# Sheet1.net
KiCad netlist of a schematic drawn in Altium Designer
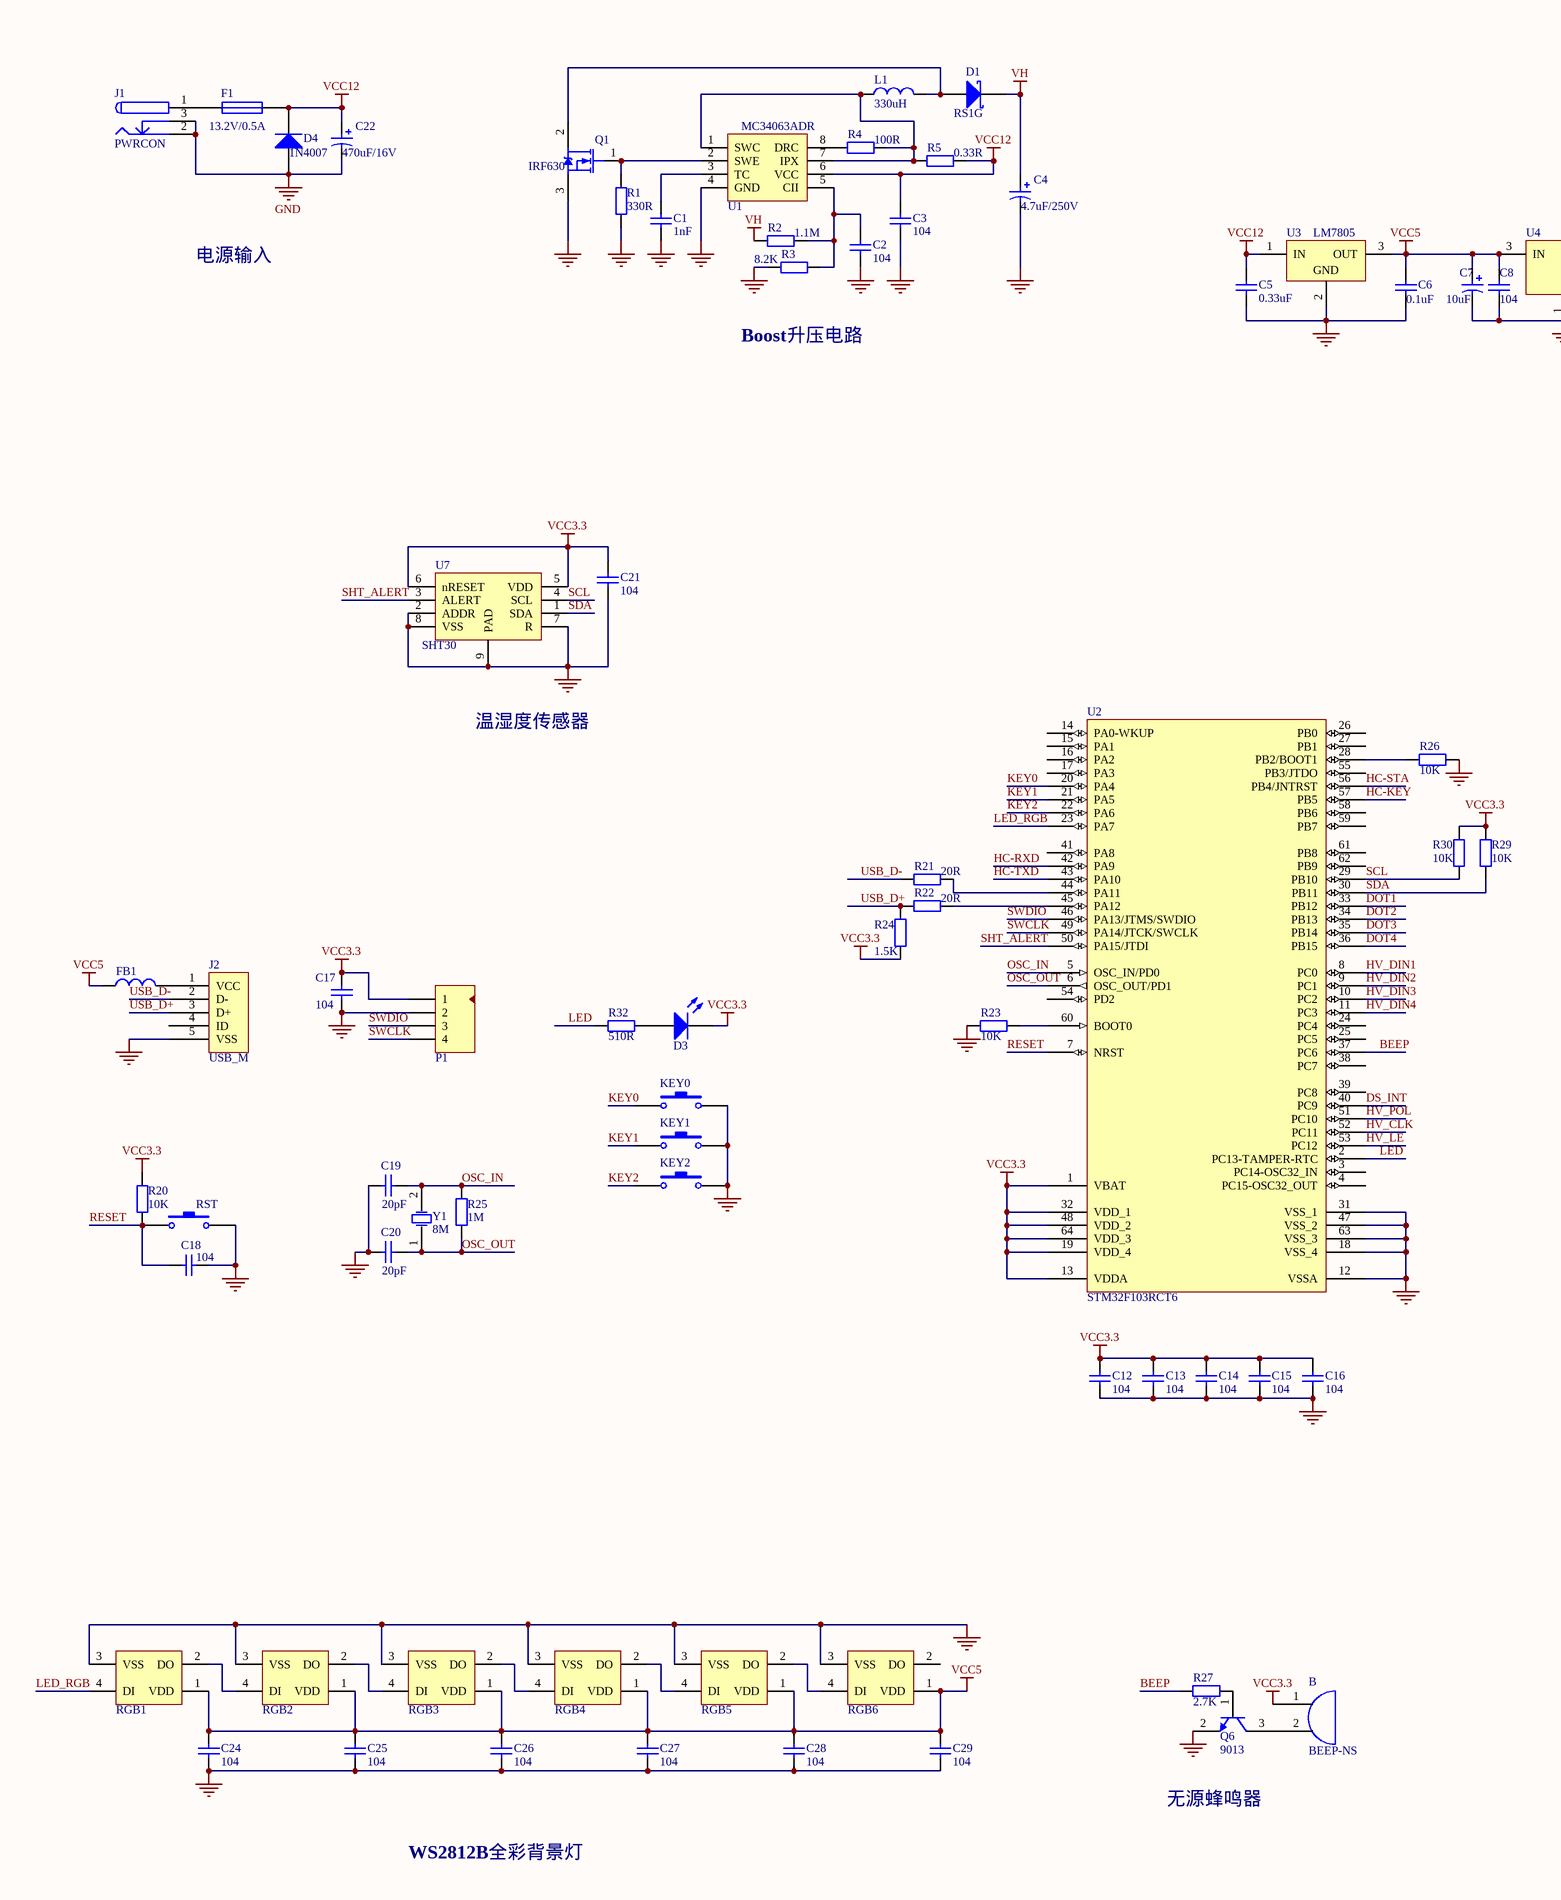
[diagram p0: Sheet1.SchDoc, left]
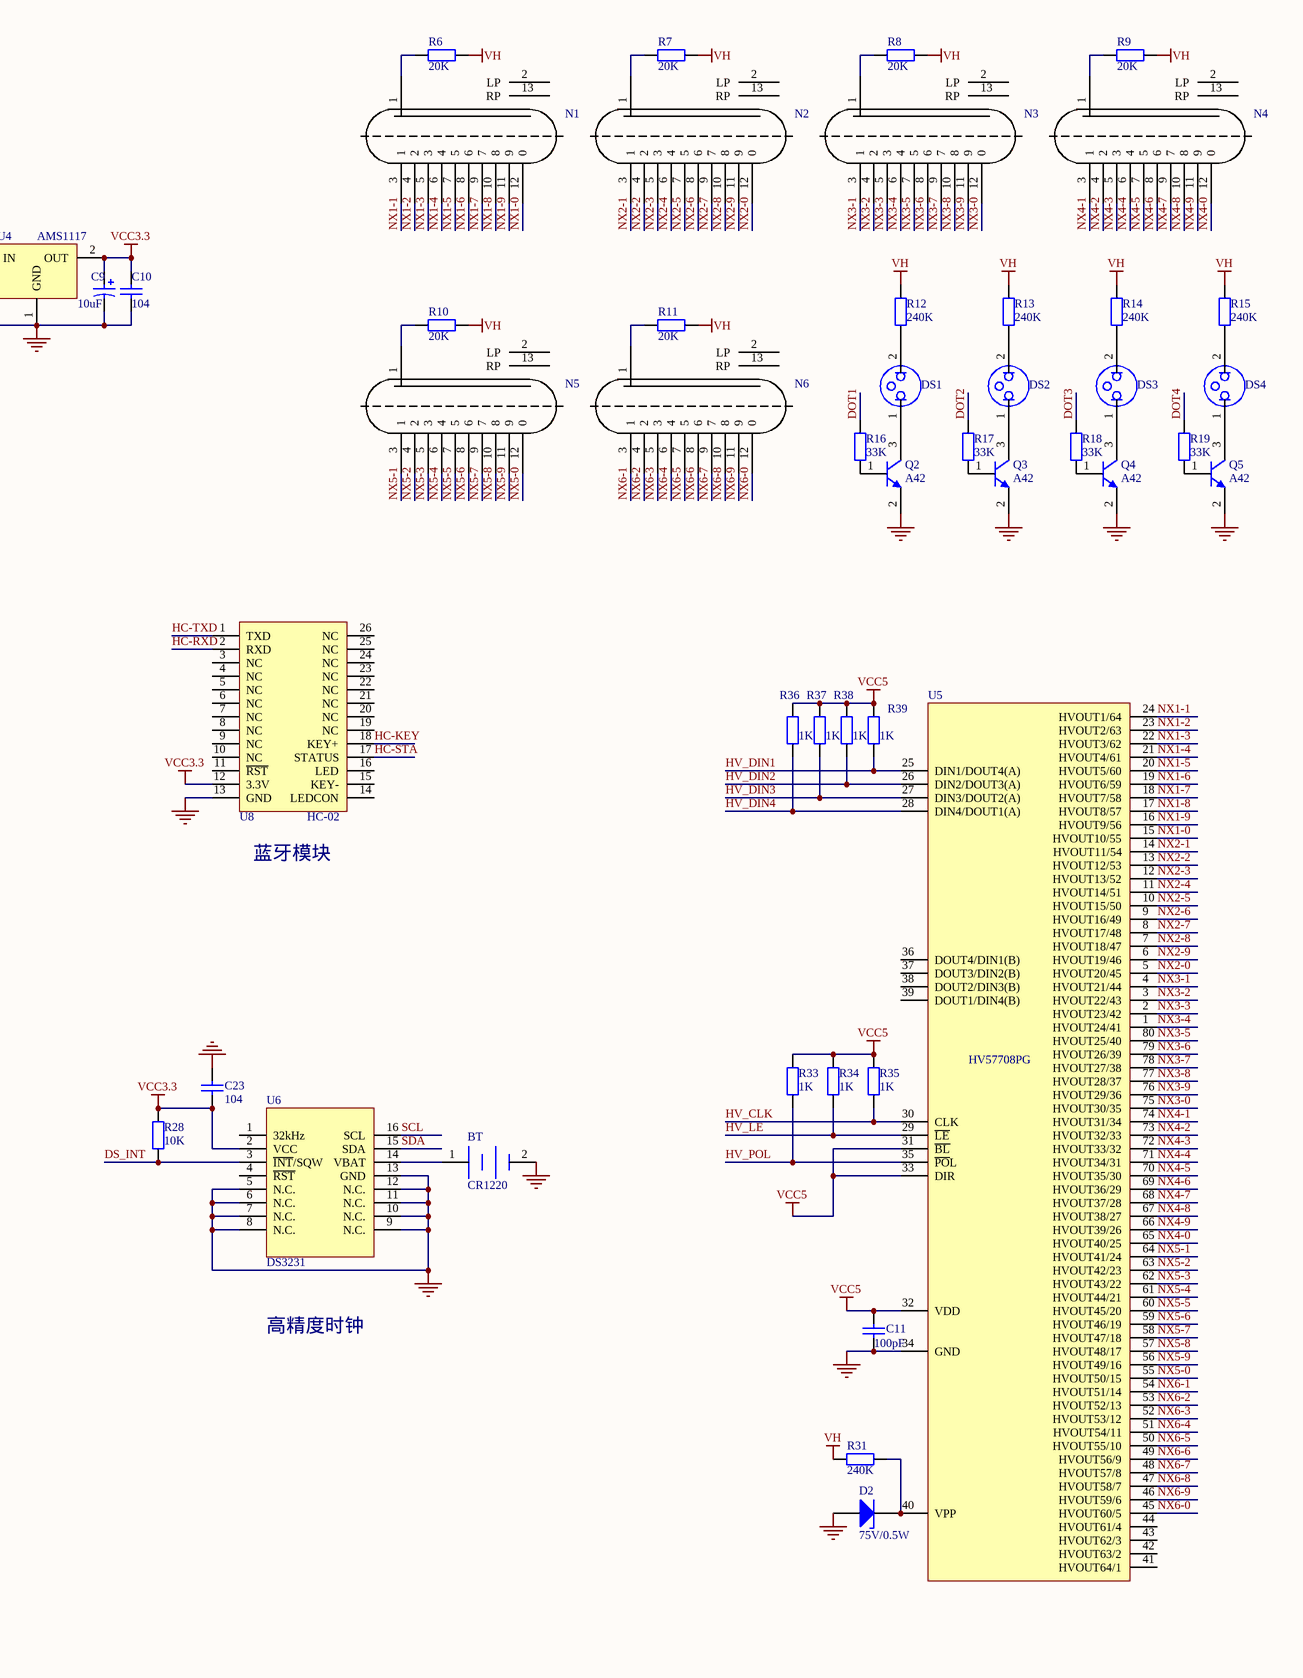
[diagram p1: Sheet1.SchDoc, right]

(export (version "E")
  (design (tool "Eeschema 10.0.6"))
  (components
    (comp (ref "B")
      (value "BEEP-NS")
      (footprint "BEEP-NS")
      (description "无源蜂鸣器")
      (libsource (lib "ChunLee") (part "BEEP-NS"))
    )
    (comp (ref "BT")
      (value "Battery")
      (footprint "CR1220")
      (fields (field (name "TYPE") "CR1220"))
      (libsource (lib "ChunLee") (part "Battery"))
    )
    (comp (ref "C1")
      (value "1nF")
      (footprint "C-0805")
      (description "贴片瓷片电容")
      (fields (field (name "Comment") "Cap-S") (field (name "PUBLISHER") "Altium Limited"))
      (libsource (lib "ChunLee") (part "Cap-S"))
    )
    (comp (ref "C2")
      (value "104")
      (footprint "C-0805")
      (description "贴片瓷片电容")
      (fields (field (name "Comment") "Cap-S") (field (name "PUBLISHER") "Altium Limited"))
      (libsource (lib "ChunLee") (part "Cap-S"))
    )
    (comp (ref "C3")
      (value "104")
      (footprint "C-0805")
      (description "贴片瓷片电容")
      (fields (field (name "Comment") "Cap-S") (field (name "PUBLISHER") "Altium Limited"))
      (libsource (lib "ChunLee") (part "Cap-S"))
    )
    (comp (ref "C4")
      (value "4.7uF/250V")
      (footprint "C-1812")
      (description "钽电容")
      (fields (field (name "Comment") "Cap-Pol") (field (name "PUBLISHER") "Altium Limited"))
      (libsource (lib "ChunLee") (part "Cap-Pol-A"))
    )
    (comp (ref "C5")
      (value "0.33uF")
      (footprint "C-1210")
      (description "贴片瓷片电容")
      (fields (field (name "Comment") "Cap-S") (field (name "PUBLISHER") "Altium Limited"))
      (libsource (lib "ChunLee") (part "Cap-S"))
    )
    (comp (ref "C6")
      (value "0.1uF")
      (footprint "C-1210")
      (description "贴片瓷片电容")
      (fields (field (name "Comment") "Cap-S") (field (name "PUBLISHER") "Altium Limited"))
      (libsource (lib "ChunLee") (part "Cap-S"))
    )
    (comp (ref "C7")
      (value "10uF")
      (footprint "C-1210")
      (description "钽电容")
      (fields (field (name "Comment") "Cap-Pol") (field (name "PUBLISHER") "Altium Limited"))
      (libsource (lib "ChunLee") (part "Cap-Pol-A"))
    )
    (comp (ref "C8")
      (value "104")
      (footprint "C-0805")
      (description "贴片瓷片电容")
      (fields (field (name "Comment") "Cap-S") (field (name "PUBLISHER") "Altium Limited"))
      (libsource (lib "ChunLee") (part "Cap-S"))
    )
    (comp (ref "C9")
      (value "10uF")
      (footprint "C-1210")
      (description "钽电容")
      (fields (field (name "Comment") "Cap-Pol") (field (name "PUBLISHER") "Altium Limited"))
      (libsource (lib "ChunLee") (part "Cap-Pol-A"))
    )
    (comp (ref "C10")
      (value "104")
      (footprint "C-0805")
      (description "贴片瓷片电容")
      (fields (field (name "Comment") "Cap-S") (field (name "PUBLISHER") "Altium Limited"))
      (libsource (lib "ChunLee") (part "Cap-S"))
    )
    (comp (ref "C11")
      (value "100pF")
      (footprint "C-0805")
      (description "贴片瓷片电容")
      (fields (field (name "Comment") "Cap-S") (field (name "PUBLISHER") "Altium Limited"))
      (libsource (lib "ChunLee") (part "Cap-S"))
    )
    (comp (ref "C12")
      (value "104")
      (footprint "C-0805")
      (description "贴片瓷片电容")
      (fields (field (name "Comment") "Cap-S") (field (name "PUBLISHER") "Altium Limited"))
      (libsource (lib "ChunLee") (part "Cap-S"))
    )
    (comp (ref "C13")
      (value "104")
      (footprint "C-0805")
      (description "贴片瓷片电容")
      (fields (field (name "Comment") "Cap-S") (field (name "PUBLISHER") "Altium Limited"))
      (libsource (lib "ChunLee") (part "Cap-S"))
    )
    (comp (ref "C14")
      (value "104")
      (footprint "C-0805")
      (description "贴片瓷片电容")
      (fields (field (name "Comment") "Cap-S") (field (name "PUBLISHER") "Altium Limited"))
      (libsource (lib "ChunLee") (part "Cap-S"))
    )
    (comp (ref "C15")
      (value "104")
      (footprint "C-0805")
      (description "贴片瓷片电容")
      (fields (field (name "Comment") "Cap-S") (field (name "PUBLISHER") "Altium Limited"))
      (libsource (lib "ChunLee") (part "Cap-S"))
    )
    (comp (ref "C16")
      (value "104")
      (footprint "C-0805")
      (description "贴片瓷片电容")
      (fields (field (name "Comment") "Cap-S") (field (name "PUBLISHER") "Altium Limited"))
      (libsource (lib "ChunLee") (part "Cap-S"))
    )
    (comp (ref "C17")
      (value "104")
      (footprint "C-0805")
      (description "贴片瓷片电容")
      (fields (field (name "Comment") "Cap-S") (field (name "PUBLISHER") "Altium Limited"))
      (libsource (lib "ChunLee") (part "Cap-S"))
    )
    (comp (ref "C18")
      (value "104")
      (footprint "C-0805")
      (description "贴片瓷片电容")
      (fields (field (name "Comment") "Cap-S") (field (name "PUBLISHER") "Altium Limited"))
      (libsource (lib "ChunLee") (part "Cap-S"))
    )
    (comp (ref "C19")
      (value "20pF")
      (footprint "C-0805")
      (description "贴片瓷片电容")
      (fields (field (name "Comment") "Cap-S") (field (name "PUBLISHER") "Altium Limited"))
      (libsource (lib "ChunLee") (part "Cap-S"))
    )
    (comp (ref "C20")
      (value "20pF")
      (footprint "C-0805")
      (description "贴片瓷片电容")
      (fields (field (name "Comment") "Cap-S") (field (name "PUBLISHER") "Altium Limited"))
      (libsource (lib "ChunLee") (part "Cap-S"))
    )
    (comp (ref "C21")
      (value "104")
      (footprint "C-0805")
      (description "贴片瓷片电容")
      (fields (field (name "Comment") "Cap-S") (field (name "PUBLISHER") "Altium Limited"))
      (libsource (lib "ChunLee") (part "Cap-S"))
    )
    (comp (ref "C22")
      (value "470uF/16V")
      (footprint "C-RB-SMD8x10.5")
      (description "贴片铝电解电容")
      (fields (field (name "Comment") "Cap-Pol-ES") (field (name "PUBLISHER") "Altium Limited"))
      (libsource (lib "ChunLee") (part "Cap-Pol-ES"))
    )
    (comp (ref "C23")
      (value "104")
      (footprint "C-0805")
      (description "贴片瓷片电容")
      (fields (field (name "Comment") "Cap-S") (field (name "PUBLISHER") "Altium Limited"))
      (libsource (lib "ChunLee") (part "Cap-S"))
    )
    (comp (ref "C24")
      (value "104")
      (footprint "C-0805")
      (description "贴片瓷片电容")
      (fields (field (name "Comment") "Cap-S") (field (name "PUBLISHER") "Altium Limited"))
      (libsource (lib "ChunLee") (part "Cap-S"))
    )
    (comp (ref "C25")
      (value "104")
      (footprint "C-0805")
      (description "贴片瓷片电容")
      (fields (field (name "Comment") "Cap-S") (field (name "PUBLISHER") "Altium Limited"))
      (libsource (lib "ChunLee") (part "Cap-S"))
    )
    (comp (ref "C26")
      (value "104")
      (footprint "C-0805")
      (description "贴片瓷片电容")
      (fields (field (name "Comment") "Cap-S") (field (name "PUBLISHER") "Altium Limited"))
      (libsource (lib "ChunLee") (part "Cap-S"))
    )
    (comp (ref "C27")
      (value "104")
      (footprint "C-0805")
      (description "贴片瓷片电容")
      (fields (field (name "Comment") "Cap-S") (field (name "PUBLISHER") "Altium Limited"))
      (libsource (lib "ChunLee") (part "Cap-S"))
    )
    (comp (ref "C28")
      (value "104")
      (footprint "C-0805")
      (description "贴片瓷片电容")
      (fields (field (name "Comment") "Cap-S") (field (name "PUBLISHER") "Altium Limited"))
      (libsource (lib "ChunLee") (part "Cap-S"))
    )
    (comp (ref "C29")
      (value "104")
      (footprint "C-0805")
      (description "贴片瓷片电容")
      (fields (field (name "Comment") "Cap-S") (field (name "PUBLISHER") "Altium Limited"))
      (libsource (lib "ChunLee") (part "Cap-S"))
    )
    (comp (ref "D1")
      (value "RS1G")
      (footprint "D-SMA")
      (description "快恢复二极管")
      (fields (field (name "PUBLISHER") "Altium Limited"))
      (libsource (lib "ChunLee") (part "Diode-Schottky"))
    )
    (comp (ref "D2")
      (value "75V/0.5W")
      (footprint "D-ll34")
      (description "稳压二极管")
      (fields (field (name "Comment") "ZMM75") (field (name "PUBLISHER") "Altium Limited"))
      (libsource (lib "ChunLee") (part "Diode-Z"))
    )
    (comp (ref "D3")
      (value "LED0")
      (footprint "LED-0805")
      (description "发光二极管")
      (fields (field (name "PUBLISHER") "Altium Limited"))
      (libsource (lib "ChunLee") (part "LED0"))
    )
    (comp (ref "D4")
      (value "1N4007")
      (footprint "D-SMA")
      (description "整流二极管")
      (fields (field (name "PUBLISHER") "Altium Limited"))
      (libsource (lib "ChunLee") (part "Diode"))
    )
    (comp (ref "DS1")
      (value "Neon")
      (footprint "PIN2")
      (description "氖泡")
      (libsource (lib "ChunLee") (part "Neon_Lamp"))
    )
    (comp (ref "DS2")
      (value "Neon")
      (footprint "PIN2")
      (description "氖泡")
      (libsource (lib "ChunLee") (part "Neon_Lamp"))
    )
    (comp (ref "DS3")
      (value "Neon")
      (footprint "PIN2")
      (description "氖泡")
      (libsource (lib "ChunLee") (part "Neon_Lamp"))
    )
    (comp (ref "DS4")
      (value "Neon")
      (footprint "PIN2")
      (description "氖泡")
      (libsource (lib "ChunLee") (part "Neon_Lamp"))
    )
    (comp (ref "F1")
      (value "13.2V/0.5A")
      (footprint "1206")
      (description "保险丝")
      (fields (field (name "Comment") "Fuse1"))
      (libsource (lib "ChunLee") (part "Fuse1"))
    )
    (comp (ref "FB1")
      (value "Inductor")
      (footprint "0805-1")
      (description "磁珠")
      (fields (field (name "PUBLISHER") "Altium Limited"))
      (libsource (lib "ChunLee") (part "Inductor"))
    )
    (comp (ref "J1")
      (value "PWRCON")
      (footprint "DC-005")
      (description "直流电源端子")
      (fields (field (name "PUBLISHER") "Altium Limited"))
      (libsource (lib "HDR_ChunLee") (part "PWRCON"))
    )
    (comp (ref "J2")
      (value "USB_M")
      (footprint "USB_MICRO")
      (description "Micro/Mini USB")
      (libsource (lib "HDR_ChunLee") (part "USB_M"))
    )
    (comp (ref "KEY0")
      (value "KEY")
      (footprint "SW_PB2_C1")
      (description "微动开关")
      (fields (field (name "PUBLISHER") "Altium Limited"))
      (libsource (lib "ChunLee") (part "SW-PB"))
    )
    (comp (ref "KEY1")
      (value "KEY")
      (footprint "SW_PB2_C1")
      (description "微动开关")
      (fields (field (name "PUBLISHER") "Altium Limited"))
      (libsource (lib "ChunLee") (part "SW-PB"))
    )
    (comp (ref "KEY2")
      (value "KEY")
      (footprint "SW_PB2_C1")
      (description "微动开关")
      (fields (field (name "PUBLISHER") "Altium Limited"))
      (libsource (lib "ChunLee") (part "SW-PB"))
    )
    (comp (ref "L1")
      (value "330uH")
      (footprint "L-SMD-12")
      (description "电感")
      (fields (field (name "Comment") "Inductor") (field (name "PUBLISHER") "Altium Limited"))
      (libsource (lib "ChunLee") (part "Inductor"))
    )
    (comp (ref "N1")
      (value "IN_14")
      (footprint "IN_14")
      (description "辉光管")
      (libsource (lib "ChunLee") (part "IN_14"))
    )
    (comp (ref "N2")
      (value "IN_14")
      (footprint "IN_14")
      (description "辉光管")
      (libsource (lib "ChunLee") (part "IN_14"))
    )
    (comp (ref "N3")
      (value "IN_14")
      (footprint "IN_14")
      (description "辉光管")
      (libsource (lib "ChunLee") (part "IN_14"))
    )
    (comp (ref "N4")
      (value "IN_14")
      (footprint "IN_14")
      (description "辉光管")
      (libsource (lib "ChunLee") (part "IN_14"))
    )
    (comp (ref "N5")
      (value "IN_14")
      (footprint "IN_14")
      (description "辉光管")
      (libsource (lib "ChunLee") (part "IN_14"))
    )
    (comp (ref "N6")
      (value "IN_14")
      (footprint "IN_14")
      (description "辉光管")
      (libsource (lib "ChunLee") (part "IN_14"))
    )
    (comp (ref "P1")
      (value "Header 4")
      (footprint "HDR4X1-2.54")
      (description "接插件")
      (fields (field (name "PUBLISHER") "Altium Limited"))
      (libsource (lib "HDR_ChunLee") (part "Header 4"))
    )
    (comp (ref "Q1")
      (value "IRF630")
      (footprint "TO263-2")
      (description "N-Channel MOSFET")
      (fields (field (name "PUBLISHER") "Altium Limited"))
      (libsource (lib "ChunLee") (part "MOSFET-N"))
    )
    (comp (ref "Q2")
      (value "A42")
      (footprint "SOT23-3")
      (description "贴片三极管")
      (fields (field (name "PUBLISHER") "Altium Limited"))
      (libsource (lib "ChunLee") (part "NPN1"))
    )
    (comp (ref "Q3")
      (value "A42")
      (footprint "SOT23-3")
      (description "贴片三极管")
      (fields (field (name "PUBLISHER") "Altium Limited"))
      (libsource (lib "ChunLee") (part "NPN1"))
    )
    (comp (ref "Q4")
      (value "A42")
      (footprint "SOT23-3")
      (description "贴片三极管")
      (fields (field (name "PUBLISHER") "Altium Limited"))
      (libsource (lib "ChunLee") (part "NPN1"))
    )
    (comp (ref "Q5")
      (value "A42")
      (footprint "SOT23-3")
      (description "贴片三极管")
      (fields (field (name "PUBLISHER") "Altium Limited"))
      (libsource (lib "ChunLee") (part "NPN1"))
    )
    (comp (ref "Q6")
      (value "9013")
      (footprint "SOT23-3")
      (description "贴片三极管")
      (fields (field (name "PUBLISHER") "Altium Limited"))
      (libsource (lib "ChunLee") (part "NPN1"))
    )
    (comp (ref "R1")
      (value "330R")
      (footprint "0805-1")
      (description "贴片电阻")
      (fields (field (name "Comment") "Res1") (field (name "PUBLISHER") "Altium Limited"))
      (libsource (lib "") (part "Res1_2"))
    )
    (comp (ref "R2")
      (value "1.1M")
      (footprint "0805-1")
      (description "贴片电阻")
      (fields (field (name "Comment") "Res1") (field (name "PUBLISHER") "Altium Limited"))
      (libsource (lib "") (part "Res1_1"))
    )
    (comp (ref "R3")
      (value "8.2K")
      (footprint "0805-1")
      (description "贴片电阻")
      (fields (field (name "Comment") "Res1") (field (name "PUBLISHER") "Altium Limited"))
      (libsource (lib "") (part "Res1_1"))
    )
    (comp (ref "R4")
      (value "100R")
      (footprint "0805-1")
      (description "贴片电阻")
      (fields (field (name "Comment") "Res1") (field (name "PUBLISHER") "Altium Limited"))
      (libsource (lib "") (part "Res1_1"))
    )
    (comp (ref "R5")
      (value "0.33R")
      (footprint "0805-1")
      (description "贴片电阻")
      (fields (field (name "Comment") "Res1") (field (name "PUBLISHER") "Altium Limited"))
      (libsource (lib "") (part "Res1_1"))
    )
    (comp (ref "R6")
      (value "20K")
      (footprint "0805-1")
      (description "贴片电阻")
      (fields (field (name "Comment") "Res1") (field (name "PUBLISHER") "Altium Limited"))
      (libsource (lib "") (part "Res1_1"))
    )
    (comp (ref "R7")
      (value "20K")
      (footprint "0805-1")
      (description "贴片电阻")
      (fields (field (name "Comment") "Res1") (field (name "PUBLISHER") "Altium Limited"))
      (libsource (lib "") (part "Res1_1"))
    )
    (comp (ref "R8")
      (value "20K")
      (footprint "0805-1")
      (description "贴片电阻")
      (fields (field (name "Comment") "Res1") (field (name "PUBLISHER") "Altium Limited"))
      (libsource (lib "") (part "Res1_1"))
    )
    (comp (ref "R9")
      (value "20K")
      (footprint "0805-1")
      (description "贴片电阻")
      (fields (field (name "Comment") "Res1") (field (name "PUBLISHER") "Altium Limited"))
      (libsource (lib "") (part "Res1_1"))
    )
    (comp (ref "R10")
      (value "20K")
      (footprint "0805-1")
      (description "贴片电阻")
      (fields (field (name "Comment") "Res1") (field (name "PUBLISHER") "Altium Limited"))
      (libsource (lib "") (part "Res1_1"))
    )
    (comp (ref "R11")
      (value "20K")
      (footprint "0805-1")
      (description "贴片电阻")
      (fields (field (name "Comment") "Res1") (field (name "PUBLISHER") "Altium Limited"))
      (libsource (lib "") (part "Res1_1"))
    )
    (comp (ref "R12")
      (value "240K")
      (footprint "0805-1")
      (description "贴片电阻")
      (fields (field (name "Comment") "Res1") (field (name "PUBLISHER") "Altium Limited"))
      (libsource (lib "ChunLee") (part "Res1"))
    )
    (comp (ref "R13")
      (value "240K")
      (footprint "0805-1")
      (description "贴片电阻")
      (fields (field (name "Comment") "Res1") (field (name "PUBLISHER") "Altium Limited"))
      (libsource (lib "ChunLee") (part "Res1"))
    )
    (comp (ref "R14")
      (value "240K")
      (footprint "0805-1")
      (description "贴片电阻")
      (fields (field (name "Comment") "Res1") (field (name "PUBLISHER") "Altium Limited"))
      (libsource (lib "") (part "Res1_2"))
    )
    (comp (ref "R15")
      (value "240K")
      (footprint "0805-1")
      (description "贴片电阻")
      (fields (field (name "Comment") "Res1") (field (name "PUBLISHER") "Altium Limited"))
      (libsource (lib "ChunLee") (part "Res1"))
    )
    (comp (ref "R16")
      (value "33K")
      (footprint "0805-1")
      (description "贴片电阻")
      (fields (field (name "Comment") "Res1") (field (name "PUBLISHER") "Altium Limited"))
      (libsource (lib "ChunLee") (part "Res1"))
    )
    (comp (ref "R17")
      (value "33K")
      (footprint "0805-1")
      (description "贴片电阻")
      (fields (field (name "Comment") "Res1") (field (name "PUBLISHER") "Altium Limited"))
      (libsource (lib "ChunLee") (part "Res1"))
    )
    (comp (ref "R18")
      (value "33K")
      (footprint "0805-1")
      (description "贴片电阻")
      (fields (field (name "Comment") "Res1") (field (name "PUBLISHER") "Altium Limited"))
      (libsource (lib "ChunLee") (part "Res1"))
    )
    (comp (ref "R19")
      (value "33K")
      (footprint "0805-1")
      (description "贴片电阻")
      (fields (field (name "Comment") "Res1") (field (name "PUBLISHER") "Altium Limited"))
      (libsource (lib "ChunLee") (part "Res1"))
    )
    (comp (ref "R20")
      (value "10K")
      (footprint "0805-1")
      (description "贴片电阻")
      (fields (field (name "Comment") "Res1") (field (name "PUBLISHER") "Altium Limited"))
      (libsource (lib "") (part "Res1_2"))
    )
    (comp (ref "R21")
      (value "20R")
      (footprint "0805-1")
      (description "贴片电阻")
      (fields (field (name "Comment") "Res1") (field (name "PUBLISHER") "Altium Limited"))
      (libsource (lib "") (part "Res1_1"))
    )
    (comp (ref "R22")
      (value "20R")
      (footprint "0805-1")
      (description "贴片电阻")
      (fields (field (name "Comment") "Res1") (field (name "PUBLISHER") "Altium Limited"))
      (libsource (lib "") (part "Res1_1"))
    )
    (comp (ref "R23")
      (value "10K")
      (footprint "0805-1")
      (description "贴片电阻")
      (fields (field (name "Comment") "Res1") (field (name "PUBLISHER") "Altium Limited"))
      (libsource (lib "") (part "Res1_1"))
    )
    (comp (ref "R24")
      (value "1.5K")
      (footprint "0805-1")
      (description "贴片电阻")
      (fields (field (name "Comment") "Res1") (field (name "PUBLISHER") "Altium Limited"))
      (libsource (lib "ChunLee") (part "Res1"))
    )
    (comp (ref "R25")
      (value "1M")
      (footprint "0805-1")
      (description "贴片电阻")
      (fields (field (name "Comment") "Res1") (field (name "PUBLISHER") "Altium Limited"))
      (libsource (lib "") (part "Res1_2"))
    )
    (comp (ref "R26")
      (value "10K")
      (footprint "0805-1")
      (description "贴片电阻")
      (fields (field (name "Comment") "Res1") (field (name "PUBLISHER") "Altium Limited"))
      (libsource (lib "") (part "Res1_1"))
    )
    (comp (ref "R27")
      (value "2.7K")
      (footprint "0805-1")
      (description "贴片电阻")
      (fields (field (name "Comment") "Res1") (field (name "PUBLISHER") "Altium Limited"))
      (libsource (lib "") (part "Res1_1"))
    )
    (comp (ref "R28")
      (value "10K")
      (footprint "0805-1")
      (description "贴片电阻")
      (fields (field (name "Comment") "Res1") (field (name "PUBLISHER") "Altium Limited"))
      (libsource (lib "") (part "Res1_2"))
    )
    (comp (ref "R29")
      (value "10K")
      (footprint "0805-1")
      (description "贴片电阻")
      (fields (field (name "Comment") "Res1") (field (name "PUBLISHER") "Altium Limited"))
      (libsource (lib "") (part "Res1_2"))
    )
    (comp (ref "R30")
      (value "10K")
      (footprint "0805-1")
      (description "贴片电阻")
      (fields (field (name "Comment") "Res1") (field (name "PUBLISHER") "Altium Limited"))
      (libsource (lib "") (part "Res1_2"))
    )
    (comp (ref "R31")
      (value "240K")
      (footprint "1206")
      (description "贴片电阻")
      (fields (field (name "Comment") "Res1") (field (name "PUBLISHER") "Altium Limited"))
      (libsource (lib "") (part "Res1_1"))
    )
    (comp (ref "R32")
      (value "510R")
      (footprint "0805-1")
      (description "贴片电阻")
      (fields (field (name "Comment") "Res1") (field (name "PUBLISHER") "Altium Limited"))
      (libsource (lib "") (part "Res1_1"))
    )
    (comp (ref "R33")
      (value "1K")
      (footprint "0805-1")
      (description "贴片电阻")
      (fields (field (name "Comment") "Res1") (field (name "PUBLISHER") "Altium Limited"))
      (libsource (lib "") (part "Res1_2"))
    )
    (comp (ref "R34")
      (value "1K")
      (footprint "0805-1")
      (description "贴片电阻")
      (fields (field (name "Comment") "Res1") (field (name "PUBLISHER") "Altium Limited"))
      (libsource (lib "") (part "Res1_2"))
    )
    (comp (ref "R35")
      (value "1K")
      (footprint "0805-1")
      (description "贴片电阻")
      (fields (field (name "Comment") "Res1") (field (name "PUBLISHER") "Altium Limited"))
      (libsource (lib "") (part "Res1_2"))
    )
    (comp (ref "R36")
      (value "1K")
      (footprint "0805-1")
      (description "贴片电阻")
      (fields (field (name "Comment") "Res1") (field (name "PUBLISHER") "Altium Limited"))
      (libsource (lib "") (part "Res1_2"))
    )
    (comp (ref "R37")
      (value "1K")
      (footprint "0805-1")
      (description "贴片电阻")
      (fields (field (name "Comment") "Res1") (field (name "PUBLISHER") "Altium Limited"))
      (libsource (lib "") (part "Res1_2"))
    )
    (comp (ref "R38")
      (value "1K")
      (footprint "0805-1")
      (description "贴片电阻")
      (fields (field (name "Comment") "Res1") (field (name "PUBLISHER") "Altium Limited"))
      (libsource (lib "") (part "Res1_2"))
    )
    (comp (ref "R39")
      (value "1K")
      (footprint "0805-1")
      (description "贴片电阻")
      (fields (field (name "Comment") "Res1") (field (name "PUBLISHER") "Altium Limited"))
      (libsource (lib "") (part "Res1_2"))
    )
    (comp (ref "RGB1")
      (value "WS2812B")
      (footprint "SMD-5050-4")
      (description "WS2812B 4脚RGB全彩LED")
      (libsource (lib "ChunLee") (part "WS2812B"))
    )
    (comp (ref "RGB2")
      (value "WS2812B")
      (footprint "SMD-5050-4")
      (description "WS2812B 4脚RGB全彩LED")
      (libsource (lib "ChunLee") (part "WS2812B"))
    )
    (comp (ref "RGB3")
      (value "WS2812B")
      (footprint "SMD-5050-4")
      (description "WS2812B 4脚RGB全彩LED")
      (libsource (lib "ChunLee") (part "WS2812B"))
    )
    (comp (ref "RGB4")
      (value "WS2812B")
      (footprint "SMD-5050-4")
      (description "WS2812B 4脚RGB全彩LED")
      (libsource (lib "ChunLee") (part "WS2812B"))
    )
    (comp (ref "RGB5")
      (value "WS2812B")
      (footprint "SMD-5050-4")
      (description "WS2812B 4脚RGB全彩LED")
      (libsource (lib "ChunLee") (part "WS2812B"))
    )
    (comp (ref "RGB6")
      (value "WS2812B")
      (footprint "SMD-5050-4")
      (description "WS2812B 4脚RGB全彩LED")
      (libsource (lib "ChunLee") (part "WS2812B"))
    )
    (comp (ref "RST")
      (value "SW-PB")
      (footprint "SW_PB2_A1")
      (description "微动开关")
      (fields (field (name "PUBLISHER") "Altium Limited"))
      (libsource (lib "ChunLee") (part "SW-PB"))
    )
    (comp (ref "U1")
      (value "MC34063ADR")
      (footprint "SOIC-8P")
      (description "开关变压器芯片")
      (libsource (lib "ChunLee") (part "MC34063ADR"))
    )
    (comp (ref "U2")
      (value "STM32F103RCT6")
      (footprint "LQFP-64")
      (description "STM32F103, 64引脚, 256Kb Flash, 48Kb SRAM")
      (fields (field (name "PUBLISHER") "Altium Limited"))
      (libsource (lib "ChunLee") (part "STM32F103RCT6"))
    )
    (comp (ref "U3")
      (value "LM7805")
      (footprint "DPAK")
      (description "Series 3-Terminal Positive Regulator")
      (libsource (lib "ChunLee") (part "LM7805CT"))
    )
    (comp (ref "U4")
      (value "AMS1117")
      (footprint "SOT223")
      (description "3.3V稳压芯片")
      (libsource (lib "ChunLee") (part "AMS1117"))
    )
    (comp (ref "U5")
      (value "HV57708PG")
      (footprint "PQFP-80")
      (description "32MHz, 64通道推挽输出串入并出芯片")
      (libsource (lib "ChunLee") (part "HV57708PG"))
    )
    (comp (ref "U6")
      (value "DS3231")
      (footprint "SOIC-16W")
      (description "高精度时钟芯片")
      (libsource (lib "ChunLee") (part "DS3231"))
    )
    (comp (ref "U7")
      (value "SHT30")
      (footprint "SHT3x-DIS")
      (description "温湿度传感器")
      (libsource (lib "ChunLee") (part "SHT3X"))
    )
    (comp (ref "U8")
      (value "HC-02")
      (footprint "HC-02")
      (description "串口蓝牙4.0, 10m")
      (libsource (lib "ChunLee") (part "HC-02"))
    )
    (comp (ref "Y1")
      (value "8M")
      (footprint "X-SM49")
      (description "晶振")
      (fields (field (name "Comment") "XTAL") (field (name "PUBLISHER") "Altium Limited"))
      (libsource (lib "ChunLee") (part "XTAL"))
    )
  )
  (nets
    (net (code "1") (name "/BEEP") (class "Default")
      (node (ref "R27") (pin "1") (pinfunction "1_1") (pintype "passive"))
      (node (ref "U2") (pin "37") (pinfunction "PC6_37") (pintype "bidirectional"))
    )
    (net (code "2") (name "/DOT1") (class "Default")
      (node (ref "R16") (pin "1") (pinfunction "1_1") (pintype "passive"))
      (node (ref "U2") (pin "33") (pinfunction "PB12_33") (pintype "bidirectional"))
    )
    (net (code "3") (name "/DOT2") (class "Default")
      (node (ref "R17") (pin "1") (pinfunction "1_1") (pintype "passive"))
      (node (ref "U2") (pin "34") (pinfunction "PB13_34") (pintype "bidirectional"))
    )
    (net (code "4") (name "/DOT3") (class "Default")
      (node (ref "R18") (pin "1") (pinfunction "1_1") (pintype "passive"))
      (node (ref "U2") (pin "35") (pinfunction "PB14_35") (pintype "bidirectional"))
    )
    (net (code "5") (name "/DOT4") (class "Default")
      (node (ref "R19") (pin "1") (pinfunction "1_1") (pintype "passive"))
      (node (ref "U2") (pin "36") (pinfunction "PB15_36") (pintype "bidirectional"))
    )
    (net (code "6") (name "/DS_INT") (class "Default")
      (node (ref "R28") (pin "1") (pinfunction "1_1") (pintype "passive"))
      (node (ref "U2") (pin "40") (pinfunction "PC9_40") (pintype "bidirectional"))
      (node (ref "U6") (pin "3") (pinfunction "~{INT}/SQW_3") (pintype "passive"))
    )
    (net (code "7") (name "/HC-KEY") (class "Default")
      (node (ref "U2") (pin "57") (pinfunction "PB5_57") (pintype "bidirectional"))
      (node (ref "U8") (pin "18") (pinfunction "KEY+_18") (pintype "passive"))
    )
    (net (code "8") (name "/HC-RXD") (class "Default")
      (node (ref "U2") (pin "42") (pinfunction "PA9_42") (pintype "bidirectional"))
      (node (ref "U8") (pin "2") (pinfunction "RXD_2") (pintype "passive"))
    )
    (net (code "9") (name "/HC-STA") (class "Default")
      (node (ref "U2") (pin "56") (pinfunction "PB4/JNTRST_56") (pintype "bidirectional"))
      (node (ref "U8") (pin "17") (pinfunction "STATUS_17") (pintype "passive"))
    )
    (net (code "10") (name "/HC-TXD") (class "Default")
      (node (ref "U2") (pin "43") (pinfunction "PA10_43") (pintype "bidirectional"))
      (node (ref "U8") (pin "1") (pinfunction "TXD_1") (pintype "passive"))
    )
    (net (code "11") (name "/HV_CLK") (class "Default")
      (node (ref "R35") (pin "1") (pinfunction "1_1") (pintype "passive"))
      (node (ref "U2") (pin "52") (pinfunction "PC11_52") (pintype "bidirectional"))
      (node (ref "U5") (pin "30") (pinfunction "CLK_30") (pintype "passive"))
    )
    (net (code "12") (name "/HV_DIN1") (class "Default")
      (node (ref "R39") (pin "1") (pinfunction "1_1") (pintype "passive"))
      (node (ref "U2") (pin "8") (pinfunction "PC0_8") (pintype "bidirectional"))
      (node (ref "U5") (pin "25") (pinfunction "DIN1/DOUT4(A)_25") (pintype "passive"))
    )
    (net (code "13") (name "/HV_DIN2") (class "Default")
      (node (ref "R38") (pin "1") (pinfunction "1_1") (pintype "passive"))
      (node (ref "U2") (pin "9") (pinfunction "PC1_9") (pintype "bidirectional"))
      (node (ref "U5") (pin "26") (pinfunction "DIN2/DOUT3(A)_26") (pintype "passive"))
    )
    (net (code "14") (name "/HV_DIN3") (class "Default")
      (node (ref "R37") (pin "1") (pinfunction "1_1") (pintype "passive"))
      (node (ref "U2") (pin "10") (pinfunction "PC2_10") (pintype "bidirectional"))
      (node (ref "U5") (pin "27") (pinfunction "DIN3/DOUT2(A)_27") (pintype "passive"))
    )
    (net (code "15") (name "/HV_DIN4") (class "Default")
      (node (ref "R36") (pin "1") (pinfunction "1_1") (pintype "passive"))
      (node (ref "U2") (pin "11") (pinfunction "PC3_11") (pintype "bidirectional"))
      (node (ref "U5") (pin "28") (pinfunction "DIN4/DOUT1(A)_28") (pintype "passive"))
    )
    (net (code "16") (name "/HV_LE") (class "Default")
      (node (ref "R34") (pin "1") (pinfunction "1_1") (pintype "passive"))
      (node (ref "U2") (pin "53") (pinfunction "PC12_53") (pintype "bidirectional"))
      (node (ref "U5") (pin "29") (pinfunction "~{LE}_29") (pintype "passive"))
    )
    (net (code "17") (name "/HV_POL") (class "Default")
      (node (ref "R33") (pin "1") (pinfunction "1_1") (pintype "passive"))
      (node (ref "U2") (pin "51") (pinfunction "PC10_51") (pintype "bidirectional"))
      (node (ref "U5") (pin "35") (pinfunction "~{PO}L_35") (pintype "passive"))
    )
    (net (code "18") (name "/KEY0") (class "Default")
      (node (ref "KEY0") (pin "1") (pinfunction "1_1") (pintype "passive"))
      (node (ref "U2") (pin "20") (pinfunction "PA4_20") (pintype "bidirectional"))
    )
    (net (code "19") (name "/KEY1") (class "Default")
      (node (ref "KEY1") (pin "1") (pinfunction "1_1") (pintype "passive"))
      (node (ref "U2") (pin "21") (pinfunction "PA5_21") (pintype "bidirectional"))
    )
    (net (code "20") (name "/KEY2") (class "Default")
      (node (ref "KEY2") (pin "1") (pinfunction "1_1") (pintype "passive"))
      (node (ref "U2") (pin "22") (pinfunction "PA6_22") (pintype "bidirectional"))
    )
    (net (code "21") (name "/LED") (class "Default")
      (node (ref "R32") (pin "1") (pinfunction "1_1") (pintype "passive"))
      (node (ref "U2") (pin "2") (pinfunction "PC13-TAMPER-RTC_2") (pintype "bidirectional"))
    )
    (net (code "22") (name "/LED_RGB") (class "Default")
      (node (ref "RGB1") (pin "4") (pinfunction "DI_4") (pintype "passive"))
      (node (ref "U2") (pin "23") (pinfunction "PA7_23") (pintype "bidirectional"))
    )
    (net (code "23") (name "/NX1-0") (class "Default")
      (node (ref "N1") (pin "12") (pinfunction "0_12") (pintype "passive"))
      (node (ref "U5") (pin "15") (pinfunction "HVOUT10/55_15") (pintype "passive"))
    )
    (net (code "24") (name "/NX1-1") (class "Default")
      (node (ref "N1") (pin "3") (pinfunction "1_3") (pintype "passive"))
      (node (ref "U5") (pin "24") (pinfunction "HVOUT1/64_24") (pintype "passive"))
    )
    (net (code "25") (name "/NX1-2") (class "Default")
      (node (ref "N1") (pin "4") (pinfunction "2_4") (pintype "passive"))
      (node (ref "U5") (pin "23") (pinfunction "HVOUT2/63_23") (pintype "passive"))
    )
    (net (code "26") (name "/NX1-3") (class "Default")
      (node (ref "N1") (pin "5") (pinfunction "3_5") (pintype "passive"))
      (node (ref "U5") (pin "22") (pinfunction "HVOUT3/62_22") (pintype "passive"))
    )
    (net (code "27") (name "/NX1-4") (class "Default")
      (node (ref "N1") (pin "6") (pinfunction "4_6") (pintype "passive"))
      (node (ref "U5") (pin "21") (pinfunction "HVOUT4/61_21") (pintype "passive"))
    )
    (net (code "28") (name "/NX1-5") (class "Default")
      (node (ref "N1") (pin "7") (pinfunction "5_7") (pintype "passive"))
      (node (ref "U5") (pin "20") (pinfunction "HVOUT5/60_20") (pintype "passive"))
    )
    (net (code "29") (name "/NX1-6") (class "Default")
      (node (ref "N1") (pin "8") (pinfunction "6_8") (pintype "passive"))
      (node (ref "U5") (pin "19") (pinfunction "HVOUT6/59_19") (pintype "passive"))
    )
    (net (code "30") (name "/NX1-7") (class "Default")
      (node (ref "N1") (pin "9") (pinfunction "7_9") (pintype "passive"))
      (node (ref "U5") (pin "18") (pinfunction "HVOUT7/58_18") (pintype "passive"))
    )
    (net (code "31") (name "/NX1-8") (class "Default")
      (node (ref "N1") (pin "10") (pinfunction "8_10") (pintype "passive"))
      (node (ref "U5") (pin "17") (pinfunction "HVOUT8/57_17") (pintype "passive"))
    )
    (net (code "32") (name "/NX1-9") (class "Default")
      (node (ref "N1") (pin "11") (pinfunction "9_11") (pintype "passive"))
      (node (ref "U5") (pin "16") (pinfunction "HVOUT9/56_16") (pintype "passive"))
    )
    (net (code "33") (name "/NX2-0") (class "Default")
      (node (ref "N2") (pin "12") (pinfunction "0_12") (pintype "passive"))
      (node (ref "U5") (pin "5") (pinfunction "HVOUT20/45_5") (pintype "passive"))
    )
    (net (code "34") (name "/NX2-1") (class "Default")
      (node (ref "N2") (pin "3") (pinfunction "1_3") (pintype "passive"))
      (node (ref "U5") (pin "14") (pinfunction "HVOUT11/54_14") (pintype "passive"))
    )
    (net (code "35") (name "/NX2-2") (class "Default")
      (node (ref "N2") (pin "4") (pinfunction "2_4") (pintype "passive"))
      (node (ref "U5") (pin "13") (pinfunction "HVOUT12/53_13") (pintype "passive"))
    )
    (net (code "36") (name "/NX2-3") (class "Default")
      (node (ref "N2") (pin "5") (pinfunction "3_5") (pintype "passive"))
      (node (ref "U5") (pin "12") (pinfunction "HVOUT13/52_12") (pintype "passive"))
    )
    (net (code "37") (name "/NX2-4") (class "Default")
      (node (ref "N2") (pin "6") (pinfunction "4_6") (pintype "passive"))
      (node (ref "U5") (pin "11") (pinfunction "HVOUT14/51_11") (pintype "passive"))
    )
    (net (code "38") (name "/NX2-5") (class "Default")
      (node (ref "N2") (pin "7") (pinfunction "5_7") (pintype "passive"))
      (node (ref "U5") (pin "10") (pinfunction "HVOUT15/50_10") (pintype "passive"))
    )
    (net (code "39") (name "/NX2-6") (class "Default")
      (node (ref "N2") (pin "8") (pinfunction "6_8") (pintype "passive"))
      (node (ref "U5") (pin "9") (pinfunction "HVOUT16/49_9") (pintype "passive"))
    )
    (net (code "40") (name "/NX2-7") (class "Default")
      (node (ref "N2") (pin "9") (pinfunction "7_9") (pintype "passive"))
      (node (ref "U5") (pin "8") (pinfunction "HVOUT17/48_8") (pintype "passive"))
    )
    (net (code "41") (name "/NX2-8") (class "Default")
      (node (ref "N2") (pin "10") (pinfunction "8_10") (pintype "passive"))
      (node (ref "U5") (pin "7") (pinfunction "HVOUT18/47_7") (pintype "passive"))
    )
    (net (code "42") (name "/NX2-9") (class "Default")
      (node (ref "N2") (pin "11") (pinfunction "9_11") (pintype "passive"))
      (node (ref "U5") (pin "6") (pinfunction "HVOUT19/46_6") (pintype "passive"))
    )
    (net (code "43") (name "/NX3-0") (class "Default")
      (node (ref "N3") (pin "12") (pinfunction "0_12") (pintype "passive"))
      (node (ref "U5") (pin "75") (pinfunction "HVOUT30/35_75") (pintype "passive"))
    )
    (net (code "44") (name "/NX3-1") (class "Default")
      (node (ref "N3") (pin "3") (pinfunction "1_3") (pintype "passive"))
      (node (ref "U5") (pin "4") (pinfunction "HVOUT21/44_4") (pintype "passive"))
    )
    (net (code "45") (name "/NX3-2") (class "Default")
      (node (ref "N3") (pin "4") (pinfunction "2_4") (pintype "passive"))
      (node (ref "U5") (pin "3") (pinfunction "HVOUT22/43_3") (pintype "passive"))
    )
    (net (code "46") (name "/NX3-3") (class "Default")
      (node (ref "N3") (pin "5") (pinfunction "3_5") (pintype "passive"))
      (node (ref "U5") (pin "2") (pinfunction "HVOUT23/42_2") (pintype "passive"))
    )
    (net (code "47") (name "/NX3-4") (class "Default")
      (node (ref "N3") (pin "6") (pinfunction "4_6") (pintype "passive"))
      (node (ref "U5") (pin "1") (pinfunction "HVOUT24/41_1") (pintype "passive"))
    )
    (net (code "48") (name "/NX3-5") (class "Default")
      (node (ref "N3") (pin "7") (pinfunction "5_7") (pintype "passive"))
      (node (ref "U5") (pin "80") (pinfunction "HVOUT25/40_80") (pintype "passive"))
    )
    (net (code "49") (name "/NX3-6") (class "Default")
      (node (ref "N3") (pin "8") (pinfunction "6_8") (pintype "passive"))
      (node (ref "U5") (pin "79") (pinfunction "HVOUT26/39_79") (pintype "passive"))
    )
    (net (code "50") (name "/NX3-7") (class "Default")
      (node (ref "N3") (pin "9") (pinfunction "7_9") (pintype "passive"))
      (node (ref "U5") (pin "78") (pinfunction "HVOUT27/38_78") (pintype "passive"))
    )
    (net (code "51") (name "/NX3-8") (class "Default")
      (node (ref "N3") (pin "10") (pinfunction "8_10") (pintype "passive"))
      (node (ref "U5") (pin "77") (pinfunction "HVOUT28/37_77") (pintype "passive"))
    )
    (net (code "52") (name "/NX3-9") (class "Default")
      (node (ref "N3") (pin "11") (pinfunction "9_11") (pintype "passive"))
      (node (ref "U5") (pin "76") (pinfunction "HVOUT29/36_76") (pintype "passive"))
    )
    (net (code "53") (name "/NX4-0") (class "Default")
      (node (ref "N4") (pin "12") (pinfunction "0_12") (pintype "passive"))
      (node (ref "U5") (pin "65") (pinfunction "HVOUT40/25_65") (pintype "passive"))
    )
    (net (code "54") (name "/NX4-1") (class "Default")
      (node (ref "N4") (pin "3") (pinfunction "1_3") (pintype "passive"))
      (node (ref "U5") (pin "74") (pinfunction "HVOUT31/34_74") (pintype "passive"))
    )
    (net (code "55") (name "/NX4-2") (class "Default")
      (node (ref "N4") (pin "4") (pinfunction "2_4") (pintype "passive"))
      (node (ref "U5") (pin "73") (pinfunction "HVOUT32/33_73") (pintype "passive"))
    )
    (net (code "56") (name "/NX4-3") (class "Default")
      (node (ref "N4") (pin "5") (pinfunction "3_5") (pintype "passive"))
      (node (ref "U5") (pin "72") (pinfunction "HVOUT33/32_72") (pintype "passive"))
    )
    (net (code "57") (name "/NX4-4") (class "Default")
      (node (ref "N4") (pin "6") (pinfunction "4_6") (pintype "passive"))
      (node (ref "U5") (pin "71") (pinfunction "HVOUT34/31_71") (pintype "passive"))
    )
    (net (code "58") (name "/NX4-5") (class "Default")
      (node (ref "N4") (pin "7") (pinfunction "5_7") (pintype "passive"))
      (node (ref "U5") (pin "70") (pinfunction "HVOUT35/30_70") (pintype "passive"))
    )
    (net (code "59") (name "/NX4-6") (class "Default")
      (node (ref "N4") (pin "8") (pinfunction "6_8") (pintype "passive"))
      (node (ref "U5") (pin "69") (pinfunction "HVOUT36/29_69") (pintype "passive"))
    )
    (net (code "60") (name "/NX4-7") (class "Default")
      (node (ref "N4") (pin "9") (pinfunction "7_9") (pintype "passive"))
      (node (ref "U5") (pin "68") (pinfunction "HVOUT37/28_68") (pintype "passive"))
    )
    (net (code "61") (name "/NX4-8") (class "Default")
      (node (ref "N4") (pin "10") (pinfunction "8_10") (pintype "passive"))
      (node (ref "U5") (pin "67") (pinfunction "HVOUT38/27_67") (pintype "passive"))
    )
    (net (code "62") (name "/NX4-9") (class "Default")
      (node (ref "N4") (pin "11") (pinfunction "9_11") (pintype "passive"))
      (node (ref "U5") (pin "66") (pinfunction "HVOUT39/26_66") (pintype "passive"))
    )
    (net (code "63") (name "/NX5-0") (class "Default")
      (node (ref "N5") (pin "12") (pinfunction "0_12") (pintype "passive"))
      (node (ref "U5") (pin "55") (pinfunction "HVOUT50/15_55") (pintype "passive"))
    )
    (net (code "64") (name "/NX5-1") (class "Default")
      (node (ref "N5") (pin "3") (pinfunction "1_3") (pintype "passive"))
      (node (ref "U5") (pin "64") (pinfunction "HVOUT41/24_64") (pintype "passive"))
    )
    (net (code "65") (name "/NX5-2") (class "Default")
      (node (ref "N5") (pin "4") (pinfunction "2_4") (pintype "passive"))
      (node (ref "U5") (pin "63") (pinfunction "HVOUT42/23_63") (pintype "passive"))
    )
    (net (code "66") (name "/NX5-3") (class "Default")
      (node (ref "N5") (pin "5") (pinfunction "3_5") (pintype "passive"))
      (node (ref "U5") (pin "62") (pinfunction "HVOUT43/22_62") (pintype "passive"))
    )
    (net (code "67") (name "/NX5-4") (class "Default")
      (node (ref "N5") (pin "6") (pinfunction "4_6") (pintype "passive"))
      (node (ref "U5") (pin "61") (pinfunction "HVOUT44/21_61") (pintype "passive"))
    )
    (net (code "68") (name "/NX5-5") (class "Default")
      (node (ref "N5") (pin "7") (pinfunction "5_7") (pintype "passive"))
      (node (ref "U5") (pin "60") (pinfunction "HVOUT45/20_60") (pintype "passive"))
    )
    (net (code "69") (name "/NX5-6") (class "Default")
      (node (ref "N5") (pin "8") (pinfunction "6_8") (pintype "passive"))
      (node (ref "U5") (pin "59") (pinfunction "HVOUT46/19_59") (pintype "passive"))
    )
    (net (code "70") (name "/NX5-7") (class "Default")
      (node (ref "N5") (pin "9") (pinfunction "7_9") (pintype "passive"))
      (node (ref "U5") (pin "58") (pinfunction "HVOUT47/18_58") (pintype "passive"))
    )
    (net (code "71") (name "/NX5-8") (class "Default")
      (node (ref "N5") (pin "10") (pinfunction "8_10") (pintype "passive"))
      (node (ref "U5") (pin "57") (pinfunction "HVOUT48/17_57") (pintype "passive"))
    )
    (net (code "72") (name "/NX5-9") (class "Default")
      (node (ref "N5") (pin "11") (pinfunction "9_11") (pintype "passive"))
      (node (ref "U5") (pin "56") (pinfunction "HVOUT49/16_56") (pintype "passive"))
    )
    (net (code "73") (name "/NX6-0") (class "Default")
      (node (ref "N6") (pin "12") (pinfunction "0_12") (pintype "passive"))
      (node (ref "U5") (pin "45") (pinfunction "HVOUT60/5_45") (pintype "passive"))
    )
    (net (code "74") (name "/NX6-1") (class "Default")
      (node (ref "N6") (pin "3") (pinfunction "1_3") (pintype "passive"))
      (node (ref "U5") (pin "54") (pinfunction "HVOUT51/14_54") (pintype "passive"))
    )
    (net (code "75") (name "/NX6-2") (class "Default")
      (node (ref "N6") (pin "4") (pinfunction "2_4") (pintype "passive"))
      (node (ref "U5") (pin "53") (pinfunction "HVOUT52/13_53") (pintype "passive"))
    )
    (net (code "76") (name "/NX6-3") (class "Default")
      (node (ref "N6") (pin "5") (pinfunction "3_5") (pintype "passive"))
      (node (ref "U5") (pin "52") (pinfunction "HVOUT53/12_52") (pintype "passive"))
    )
    (net (code "77") (name "/NX6-4") (class "Default")
      (node (ref "N6") (pin "6") (pinfunction "4_6") (pintype "passive"))
      (node (ref "U5") (pin "51") (pinfunction "HVOUT54/11_51") (pintype "passive"))
    )
    (net (code "78") (name "/NX6-5") (class "Default")
      (node (ref "N6") (pin "7") (pinfunction "5_7") (pintype "passive"))
      (node (ref "U5") (pin "50") (pinfunction "HVOUT55/10_50") (pintype "passive"))
    )
    (net (code "79") (name "/NX6-6") (class "Default")
      (node (ref "N6") (pin "8") (pinfunction "6_8") (pintype "passive"))
      (node (ref "U5") (pin "49") (pinfunction "HVOUT56/9_49") (pintype "passive"))
    )
    (net (code "80") (name "/NX6-7") (class "Default")
      (node (ref "N6") (pin "9") (pinfunction "7_9") (pintype "passive"))
      (node (ref "U5") (pin "48") (pinfunction "HVOUT57/8_48") (pintype "passive"))
    )
    (net (code "81") (name "/NX6-8") (class "Default")
      (node (ref "N6") (pin "10") (pinfunction "8_10") (pintype "passive"))
      (node (ref "U5") (pin "47") (pinfunction "HVOUT58/7_47") (pintype "passive"))
    )
    (net (code "82") (name "/NX6-9") (class "Default")
      (node (ref "N6") (pin "11") (pinfunction "9_11") (pintype "passive"))
      (node (ref "U5") (pin "46") (pinfunction "HVOUT59/6_46") (pintype "passive"))
    )
    (net (code "83") (name "/OSC_IN") (class "Default")
      (node (ref "C19") (pin "2") (pinfunction "2_2") (pintype "passive"))
      (node (ref "R25") (pin "2") (pinfunction "2_2") (pintype "passive"))
      (node (ref "U2") (pin "5") (pinfunction "OSC_IN/PD0_5") (pintype "input"))
      (node (ref "Y1") (pin "2") (pinfunction "OSC2_2") (pintype "passive"))
    )
    (net (code "84") (name "/OSC_OUT") (class "Default")
      (node (ref "C20") (pin "2") (pinfunction "2_2") (pintype "passive"))
      (node (ref "R25") (pin "1") (pinfunction "1_1") (pintype "passive"))
      (node (ref "U2") (pin "6") (pinfunction "OSC_OUT/PD1_6") (pintype "output"))
      (node (ref "Y1") (pin "1") (pinfunction "OSC1_1") (pintype "passive"))
    )
    (net (code "85") (name "/RESET") (class "Default")
      (node (ref "C18") (pin "1") (pinfunction "1_1") (pintype "passive"))
      (node (ref "R20") (pin "1") (pinfunction "1_1") (pintype "passive"))
      (node (ref "RST") (pin "1") (pinfunction "1_1") (pintype "passive"))
      (node (ref "U2") (pin "7") (pinfunction "NRST_7") (pintype "bidirectional"))
    )
    (net (code "86") (name "/SCL") (class "Default")
      (node (ref "R30") (pin "1") (pinfunction "1_1") (pintype "passive"))
      (node (ref "U2") (pin "29") (pinfunction "PB10_29") (pintype "bidirectional"))
      (node (ref "U6") (pin "16") (pinfunction "SCL_16") (pintype "passive"))
      (node (ref "U7") (pin "4") (pinfunction "SCL_4") (pintype "passive"))
    )
    (net (code "87") (name "/SDA") (class "Default")
      (node (ref "R29") (pin "1") (pinfunction "1_1") (pintype "passive"))
      (node (ref "U2") (pin "30") (pinfunction "PB11_30") (pintype "bidirectional"))
      (node (ref "U6") (pin "15") (pinfunction "SDA_15") (pintype "passive"))
      (node (ref "U7") (pin "1") (pinfunction "SDA_1") (pintype "passive"))
    )
    (net (code "88") (name "/SHT_ALERT") (class "Default")
      (node (ref "U2") (pin "50") (pinfunction "PA15/JTDI_50") (pintype "bidirectional"))
      (node (ref "U7") (pin "3") (pinfunction "ALERT_3") (pintype "passive"))
    )
    (net (code "89") (name "/SWCLK") (class "Default")
      (node (ref "P1") (pin "4") (pinfunction "4_4") (pintype "passive"))
      (node (ref "U2") (pin "49") (pinfunction "PA14/JTCK/SWCLK_49") (pintype "bidirectional"))
    )
    (net (code "90") (name "/SWDIO") (class "Default")
      (node (ref "P1") (pin "3") (pinfunction "3_3") (pintype "passive"))
      (node (ref "U2") (pin "46") (pinfunction "PA13/JTMS/SWDIO_46") (pintype "bidirectional"))
    )
    (net (code "91") (name "/USB_D+") (class "Default")
      (node (ref "J2") (pin "3") (pinfunction "D+_3") (pintype "passive"))
      (node (ref "R22") (pin "1") (pinfunction "1_1") (pintype "passive"))
      (node (ref "R24") (pin "1") (pinfunction "1_1") (pintype "passive"))
    )
    (net (code "92") (name "/USB_D-") (class "Default")
      (node (ref "J2") (pin "2") (pinfunction "D-_2") (pintype "passive"))
      (node (ref "R21") (pin "1") (pinfunction "1_1") (pintype "passive"))
    )
    (net (code "93") (name "GND") (class "Default")
      (node (ref "BT") (pin "2") (pintype "passive"))
      (node (ref "C1") (pin "1") (pinfunction "1_1") (pintype "passive"))
      (node (ref "C10") (pin "2") (pinfunction "2_2") (pintype "passive"))
      (node (ref "C11") (pin "2") (pinfunction "2_2") (pintype "passive"))
      (node (ref "C12") (pin "1") (pinfunction "1_1") (pintype "passive"))
      (node (ref "C13") (pin "1") (pinfunction "1_1") (pintype "passive"))
      (node (ref "C14") (pin "1") (pinfunction "1_1") (pintype "passive"))
      (node (ref "C15") (pin "1") (pinfunction "1_1") (pintype "passive"))
      (node (ref "C16") (pin "1") (pinfunction "1_1") (pintype "passive"))
      (node (ref "C17") (pin "2") (pinfunction "2_2") (pintype "passive"))
      (node (ref "C18") (pin "2") (pinfunction "2_2") (pintype "passive"))
      (node (ref "C19") (pin "1") (pinfunction "1_1") (pintype "passive"))
      (node (ref "C2") (pin "1") (pinfunction "1_1") (pintype "passive"))
      (node (ref "C20") (pin "1") (pinfunction "1_1") (pintype "passive"))
      (node (ref "C21") (pin "1") (pinfunction "1_1") (pintype "passive"))
      (node (ref "C22") (pin "2") (pinfunction "2_2") (pintype "passive"))
      (node (ref "C23") (pin "2") (pinfunction "2_2") (pintype "passive"))
      (node (ref "C24") (pin "2") (pinfunction "2_2") (pintype "passive"))
      (node (ref "C25") (pin "2") (pinfunction "2_2") (pintype "passive"))
      (node (ref "C26") (pin "2") (pinfunction "2_2") (pintype "passive"))
      (node (ref "C27") (pin "2") (pinfunction "2_2") (pintype "passive"))
      (node (ref "C28") (pin "2") (pinfunction "2_2") (pintype "passive"))
      (node (ref "C29") (pin "2") (pinfunction "2_2") (pintype "passive"))
      (node (ref "C3") (pin "1") (pinfunction "1_1") (pintype "passive"))
      (node (ref "C4") (pin "2") (pinfunction "2_2") (pintype "passive"))
      (node (ref "C5") (pin "1") (pinfunction "1_1") (pintype "passive"))
      (node (ref "C6") (pin "1") (pinfunction "1_1") (pintype "passive"))
      (node (ref "C7") (pin "2") (pinfunction "2_2") (pintype "passive"))
      (node (ref "C8") (pin "2") (pinfunction "2_2") (pintype "passive"))
      (node (ref "C9") (pin "2") (pinfunction "2_2") (pintype "passive"))
      (node (ref "D2") (pin "1") (pinfunction "A_1") (pintype "passive"))
      (node (ref "D4") (pin "1") (pinfunction "A_1") (pintype "passive"))
      (node (ref "J1") (pin "2") (pinfunction "2_2") (pintype "power_in"))
      (node (ref "J1") (pin "3") (pinfunction "3_3") (pintype "power_in"))
      (node (ref "J2") (pin "5") (pinfunction "VSS_5") (pintype "passive"))
      (node (ref "KEY0") (pin "2") (pinfunction "2_2") (pintype "passive"))
      (node (ref "KEY1") (pin "2") (pinfunction "2_2") (pintype "passive"))
      (node (ref "KEY2") (pin "2") (pinfunction "2_2") (pintype "passive"))
      (node (ref "P1") (pin "2") (pinfunction "2_2") (pintype "passive"))
      (node (ref "Q1") (pin "3") (pinfunction "S_3") (pintype "passive"))
      (node (ref "Q2") (pin "2") (pinfunction "E_2") (pintype "passive"))
      (node (ref "Q3") (pin "2") (pinfunction "E_2") (pintype "passive"))
      (node (ref "Q4") (pin "2") (pinfunction "E_2") (pintype "passive"))
      (node (ref "Q5") (pin "2") (pinfunction "E_2") (pintype "passive"))
      (node (ref "Q6") (pin "2") (pinfunction "E_2") (pintype "passive"))
      (node (ref "R1") (pin "1") (pinfunction "1_1") (pintype "passive"))
      (node (ref "R23") (pin "1") (pinfunction "1_1") (pintype "passive"))
      (node (ref "R26") (pin "2") (pinfunction "2_2") (pintype "passive"))
      (node (ref "R3") (pin "1") (pinfunction "1_1") (pintype "passive"))
      (node (ref "RGB1") (pin "3") (pinfunction "VSS_3") (pintype "passive"))
      (node (ref "RGB2") (pin "3") (pinfunction "VSS_3") (pintype "passive"))
      (node (ref "RGB3") (pin "3") (pinfunction "VSS_3") (pintype "passive"))
      (node (ref "RGB4") (pin "3") (pinfunction "VSS_3") (pintype "passive"))
      (node (ref "RGB5") (pin "3") (pinfunction "VSS_3") (pintype "passive"))
      (node (ref "RGB6") (pin "3") (pinfunction "VSS_3") (pintype "passive"))
      (node (ref "RST") (pin "2") (pinfunction "2_2") (pintype "passive"))
      (node (ref "U1") (pin "4") (pinfunction "GND_4") (pintype "passive"))
      (node (ref "U2") (pin "12") (pinfunction "VSSA_12") (pintype "power_in"))
      (node (ref "U2") (pin "18") (pinfunction "VSS_4_18") (pintype "power_in"))
      (node (ref "U2") (pin "31") (pinfunction "VSS_1_31") (pintype "power_in"))
      (node (ref "U2") (pin "47") (pinfunction "VSS_2_47") (pintype "power_in"))
      (node (ref "U2") (pin "63") (pinfunction "VSS_3_63") (pintype "power_in"))
      (node (ref "U3") (pin "2") (pinfunction "GND_2") (pintype "power_in"))
      (node (ref "U4") (pin "1") (pinfunction "GND_1") (pintype "passive"))
      (node (ref "U5") (pin "34") (pinfunction "GND_34") (pintype "passive"))
      (node (ref "U6") (pin "10") (pinfunction "N.C._10") (pintype "passive"))
      (node (ref "U6") (pin "11") (pinfunction "N.C._11") (pintype "passive"))
      (node (ref "U6") (pin "12") (pinfunction "N.C._12") (pintype "passive"))
      (node (ref "U6") (pin "13") (pinfunction "GND_13") (pintype "passive"))
      (node (ref "U6") (pin "5") (pinfunction "N.C._5") (pintype "passive"))
      (node (ref "U6") (pin "6") (pinfunction "N.C._6") (pintype "passive"))
      (node (ref "U6") (pin "7") (pinfunction "N.C._7") (pintype "passive"))
      (node (ref "U6") (pin "8") (pinfunction "N.C._8") (pintype "passive"))
      (node (ref "U6") (pin "9") (pinfunction "N.C._9") (pintype "passive"))
      (node (ref "U7") (pin "2") (pinfunction "ADDR_2") (pintype "passive"))
      (node (ref "U7") (pin "7") (pinfunction "R_7") (pintype "passive"))
      (node (ref "U7") (pin "8") (pinfunction "VSS_8") (pintype "passive"))
      (node (ref "U7") (pin "9") (pinfunction "PAD_9") (pintype "passive"))
      (node (ref "U8") (pin "13") (pinfunction "GND_13") (pintype "passive"))
    )
    (net (code "94") (name "Net-(B-1)") (class "Default")
      (node (ref "B") (pin "2") (pinfunction "1_2") (pintype "passive"))
      (node (ref "Q6") (pin "3") (pinfunction "C_3") (pintype "passive"))
    )
    (net (code "95") (name "Net-(D1-A)") (class "Default")
      (node (ref "D1") (pin "1") (pinfunction "A_1") (pintype "passive"))
      (node (ref "L1") (pin "2") (pinfunction "2_2") (pintype "passive"))
      (node (ref "Q1") (pin "2") (pinfunction "D_2") (pintype "passive"))
    )
    (net (code "96") (name "Net-(D2-K)") (class "Default")
      (node (ref "D2") (pin "2") (pinfunction "K_2") (pintype "passive"))
      (node (ref "R31") (pin "2") (pinfunction "2_2") (pintype "passive"))
      (node (ref "U5") (pin "40") (pinfunction "VPP_40") (pintype "passive"))
    )
    (net (code "97") (name "Net-(D3-A)") (class "Default")
      (node (ref "D3") (pin "1") (pinfunction "A_1") (pintype "passive"))
      (node (ref "R32") (pin "2") (pinfunction "2_2") (pintype "passive"))
    )
    (net (code "98") (name "Net-(DS1-Pad2)") (class "Default")
      (node (ref "DS1") (pin "2") (pintype "passive"))
      (node (ref "R12") (pin "2") (pinfunction "2_2") (pintype "passive"))
    )
    (net (code "99") (name "Net-(DS2-Pad2)") (class "Default")
      (node (ref "DS2") (pin "2") (pintype "passive"))
      (node (ref "R13") (pin "2") (pinfunction "2_2") (pintype "passive"))
    )
    (net (code "100") (name "Net-(DS3-Pad2)") (class "Default")
      (node (ref "DS3") (pin "2") (pintype "passive"))
      (node (ref "R14") (pin "1") (pinfunction "1_1") (pintype "passive"))
    )
    (net (code "101") (name "Net-(DS4-Pad2)") (class "Default")
      (node (ref "DS4") (pin "2") (pintype "passive"))
      (node (ref "R15") (pin "2") (pinfunction "2_2") (pintype "passive"))
    )
    (net (code "102") (name "Net-(F1-Pad1)") (class "Default")
      (node (ref "F1") (pin "1") (pinfunction "1_1") (pintype "passive"))
      (node (ref "J1") (pin "1") (pinfunction "1_1") (pintype "power_in"))
    )
    (net (code "103") (name "Net-(J2-VCC)") (class "Default")
      (node (ref "FB1") (pin "2") (pinfunction "2_2") (pintype "passive"))
      (node (ref "J2") (pin "1") (pinfunction "VCC_1") (pintype "passive"))
    )
    (net (code "104") (name "Net-(N1-VCC)") (class "Default")
      (node (ref "N1") (pin "1") (pinfunction "VCC_1") (pintype "passive"))
      (node (ref "R6") (pin "1") (pinfunction "1_1") (pintype "passive"))
    )
    (net (code "105") (name "Net-(N2-VCC)") (class "Default")
      (node (ref "N2") (pin "1") (pinfunction "VCC_1") (pintype "passive"))
      (node (ref "R7") (pin "1") (pinfunction "1_1") (pintype "passive"))
    )
    (net (code "106") (name "Net-(N3-VCC)") (class "Default")
      (node (ref "N3") (pin "1") (pinfunction "VCC_1") (pintype "passive"))
      (node (ref "R8") (pin "1") (pinfunction "1_1") (pintype "passive"))
    )
    (net (code "107") (name "Net-(N4-VCC)") (class "Default")
      (node (ref "N4") (pin "1") (pinfunction "VCC_1") (pintype "passive"))
      (node (ref "R9") (pin "1") (pinfunction "1_1") (pintype "passive"))
    )
    (net (code "108") (name "Net-(N5-VCC)") (class "Default")
      (node (ref "N5") (pin "1") (pinfunction "VCC_1") (pintype "passive"))
      (node (ref "R10") (pin "1") (pinfunction "1_1") (pintype "passive"))
    )
    (net (code "109") (name "Net-(N6-VCC)") (class "Default")
      (node (ref "N6") (pin "1") (pinfunction "VCC_1") (pintype "passive"))
      (node (ref "R11") (pin "1") (pinfunction "1_1") (pintype "passive"))
    )
    (net (code "110") (name "Net-(Q1-G)") (class "Default")
      (node (ref "Q1") (pin "1") (pinfunction "G_1") (pintype "passive"))
      (node (ref "R1") (pin "2") (pinfunction "2_2") (pintype "passive"))
      (node (ref "U1") (pin "2") (pinfunction "SWE_2") (pintype "passive"))
    )
    (net (code "111") (name "Net-(Q2-B)") (class "Default")
      (node (ref "Q2") (pin "1") (pinfunction "B_1") (pintype "passive"))
      (node (ref "R16") (pin "2") (pinfunction "2_2") (pintype "passive"))
    )
    (net (code "112") (name "Net-(Q2-C)") (class "Default")
      (node (ref "DS1") (pin "1") (pintype "passive"))
      (node (ref "Q2") (pin "3") (pinfunction "C_3") (pintype "passive"))
    )
    (net (code "113") (name "Net-(Q3-B)") (class "Default")
      (node (ref "Q3") (pin "1") (pinfunction "B_1") (pintype "passive"))
      (node (ref "R17") (pin "2") (pinfunction "2_2") (pintype "passive"))
    )
    (net (code "114") (name "Net-(Q3-C)") (class "Default")
      (node (ref "DS2") (pin "1") (pintype "passive"))
      (node (ref "Q3") (pin "3") (pinfunction "C_3") (pintype "passive"))
    )
    (net (code "115") (name "Net-(Q4-B)") (class "Default")
      (node (ref "Q4") (pin "1") (pinfunction "B_1") (pintype "passive"))
      (node (ref "R18") (pin "2") (pinfunction "2_2") (pintype "passive"))
    )
    (net (code "116") (name "Net-(Q4-C)") (class "Default")
      (node (ref "DS3") (pin "1") (pintype "passive"))
      (node (ref "Q4") (pin "3") (pinfunction "C_3") (pintype "passive"))
    )
    (net (code "117") (name "Net-(Q5-B)") (class "Default")
      (node (ref "Q5") (pin "1") (pinfunction "B_1") (pintype "passive"))
      (node (ref "R19") (pin "2") (pinfunction "2_2") (pintype "passive"))
    )
    (net (code "118") (name "Net-(Q5-C)") (class "Default")
      (node (ref "DS4") (pin "1") (pintype "passive"))
      (node (ref "Q5") (pin "3") (pinfunction "C_3") (pintype "passive"))
    )
    (net (code "119") (name "Net-(Q6-B)") (class "Default")
      (node (ref "Q6") (pin "1") (pinfunction "B_1") (pintype "passive"))
      (node (ref "R27") (pin "2") (pinfunction "2_2") (pintype "passive"))
    )
    (net (code "120") (name "Net-(RGB1-DO)") (class "Default")
      (node (ref "RGB1") (pin "2") (pinfunction "DO_2") (pintype "passive"))
      (node (ref "RGB2") (pin "4") (pinfunction "DI_4") (pintype "passive"))
    )
    (net (code "121") (name "Net-(RGB2-DO)") (class "Default")
      (node (ref "RGB2") (pin "2") (pinfunction "DO_2") (pintype "passive"))
      (node (ref "RGB3") (pin "4") (pinfunction "DI_4") (pintype "passive"))
    )
    (net (code "122") (name "Net-(RGB3-DO)") (class "Default")
      (node (ref "RGB3") (pin "2") (pinfunction "DO_2") (pintype "passive"))
      (node (ref "RGB4") (pin "4") (pinfunction "DI_4") (pintype "passive"))
    )
    (net (code "123") (name "Net-(RGB4-DO)") (class "Default")
      (node (ref "RGB4") (pin "2") (pinfunction "DO_2") (pintype "passive"))
      (node (ref "RGB5") (pin "4") (pinfunction "DI_4") (pintype "passive"))
    )
    (net (code "124") (name "Net-(RGB5-DO)") (class "Default")
      (node (ref "RGB5") (pin "2") (pinfunction "DO_2") (pintype "passive"))
      (node (ref "RGB6") (pin "4") (pinfunction "DI_4") (pintype "passive"))
    )
    (net (code "125") (name "Net-(U1-CII)") (class "Default")
      (node (ref "C2") (pin "2") (pinfunction "2_2") (pintype "passive"))
      (node (ref "R2") (pin "2") (pinfunction "2_2") (pintype "passive"))
      (node (ref "R3") (pin "2") (pinfunction "2_2") (pintype "passive"))
      (node (ref "U1") (pin "5") (pinfunction "CII_5") (pintype "passive"))
    )
    (net (code "126") (name "Net-(U1-DRC)") (class "Default")
      (node (ref "R4") (pin "1") (pinfunction "1_1") (pintype "passive"))
      (node (ref "U1") (pin "8") (pinfunction "DRC_8") (pintype "passive"))
    )
    (net (code "127") (name "Net-(U1-IPX)") (class "Default")
      (node (ref "L1") (pin "1") (pinfunction "1_1") (pintype "passive"))
      (node (ref "R4") (pin "2") (pinfunction "2_2") (pintype "passive"))
      (node (ref "R5") (pin "1") (pinfunction "1_1") (pintype "passive"))
      (node (ref "U1") (pin "1") (pinfunction "SWC_1") (pintype "passive"))
      (node (ref "U1") (pin "7") (pinfunction "IPX_7") (pintype "passive"))
    )
    (net (code "128") (name "Net-(U1-TC)") (class "Default")
      (node (ref "C1") (pin "2") (pinfunction "2_2") (pintype "passive"))
      (node (ref "U1") (pin "3") (pinfunction "TC_3") (pintype "passive"))
    )
    (net (code "129") (name "Net-(U2-BOOT0)") (class "Default")
      (node (ref "R23") (pin "2") (pinfunction "2_2") (pintype "passive"))
      (node (ref "U2") (pin "60") (pinfunction "BOOT0_60") (pintype "input"))
    )
    (net (code "130") (name "Net-(U2-PA11)") (class "Default")
      (node (ref "R21") (pin "2") (pinfunction "2_2") (pintype "passive"))
      (node (ref "U2") (pin "44") (pinfunction "PA11_44") (pintype "bidirectional"))
    )
    (net (code "131") (name "Net-(U2-PA12)") (class "Default")
      (node (ref "R22") (pin "2") (pinfunction "2_2") (pintype "passive"))
      (node (ref "U2") (pin "45") (pinfunction "PA12_45") (pintype "bidirectional"))
    )
    (net (code "132") (name "Net-(U2-PB2{slash}BOOT1)") (class "Default")
      (node (ref "R26") (pin "1") (pinfunction "1_1") (pintype "passive"))
      (node (ref "U2") (pin "28") (pinfunction "PB2/BOOT1_28") (pintype "bidirectional"))
    )
    (net (code "133") (name "Net-(U6-VBAT)") (class "Default")
      (node (ref "BT") (pin "1") (pintype "passive"))
      (node (ref "U6") (pin "14") (pinfunction "VBAT_14") (pintype "passive"))
    )
    (net (code "134") (name "VCC3.3") (class "Default")
      (node (ref "B") (pin "1") (pinfunction "0_1") (pintype "passive"))
      (node (ref "C10") (pin "1") (pinfunction "1_1") (pintype "passive"))
      (node (ref "C12") (pin "2") (pinfunction "2_2") (pintype "passive"))
      (node (ref "C13") (pin "2") (pinfunction "2_2") (pintype "passive"))
      (node (ref "C14") (pin "2") (pinfunction "2_2") (pintype "passive"))
      (node (ref "C15") (pin "2") (pinfunction "2_2") (pintype "passive"))
      (node (ref "C16") (pin "2") (pinfunction "2_2") (pintype "passive"))
      (node (ref "C17") (pin "1") (pinfunction "1_1") (pintype "passive"))
      (node (ref "C21") (pin "2") (pinfunction "2_2") (pintype "passive"))
      (node (ref "C23") (pin "1") (pinfunction "1_1") (pintype "passive"))
      (node (ref "C9") (pin "1") (pinfunction "1_1") (pintype "passive"))
      (node (ref "D3") (pin "2") (pinfunction "K_2") (pintype "passive"))
      (node (ref "P1") (pin "1") (pinfunction "1_1") (pintype "passive"))
      (node (ref "R20") (pin "2") (pinfunction "2_2") (pintype "passive"))
      (node (ref "R24") (pin "2") (pinfunction "2_2") (pintype "passive"))
      (node (ref "R28") (pin "2") (pinfunction "2_2") (pintype "passive"))
      (node (ref "R29") (pin "2") (pinfunction "2_2") (pintype "passive"))
      (node (ref "R30") (pin "2") (pinfunction "2_2") (pintype "passive"))
      (node (ref "U2") (pin "1") (pinfunction "VBAT_1") (pintype "power_in"))
      (node (ref "U2") (pin "13") (pinfunction "VDDA_13") (pintype "power_in"))
      (node (ref "U2") (pin "19") (pinfunction "VDD_4_19") (pintype "power_in"))
      (node (ref "U2") (pin "32") (pinfunction "VDD_1_32") (pintype "power_in"))
      (node (ref "U2") (pin "48") (pinfunction "VDD_2_48") (pintype "power_in"))
      (node (ref "U2") (pin "64") (pinfunction "VDD_3_64") (pintype "power_in"))
      (node (ref "U4") (pin "2") (pinfunction "OUT_2") (pintype "passive"))
      (node (ref "U6") (pin "2") (pinfunction "VCC_2") (pintype "passive"))
      (node (ref "U7") (pin "5") (pinfunction "VDD_5") (pintype "passive"))
      (node (ref "U7") (pin "6") (pinfunction "nRESET_6") (pintype "passive"))
      (node (ref "U8") (pin "12") (pinfunction "3.3V_12") (pintype "passive"))
    )
    (net (code "135") (name "VCC5") (class "Default")
      (node (ref "C11") (pin "1") (pinfunction "1_1") (pintype "passive"))
      (node (ref "C24") (pin "1") (pinfunction "1_1") (pintype "passive"))
      (node (ref "C25") (pin "1") (pinfunction "1_1") (pintype "passive"))
      (node (ref "C26") (pin "1") (pinfunction "1_1") (pintype "passive"))
      (node (ref "C27") (pin "1") (pinfunction "1_1") (pintype "passive"))
      (node (ref "C28") (pin "1") (pinfunction "1_1") (pintype "passive"))
      (node (ref "C29") (pin "1") (pinfunction "1_1") (pintype "passive"))
      (node (ref "C6") (pin "2") (pinfunction "2_2") (pintype "passive"))
      (node (ref "C7") (pin "1") (pinfunction "1_1") (pintype "passive"))
      (node (ref "C8") (pin "1") (pinfunction "1_1") (pintype "passive"))
      (node (ref "FB1") (pin "1") (pinfunction "1_1") (pintype "passive"))
      (node (ref "R33") (pin "2") (pinfunction "2_2") (pintype "passive"))
      (node (ref "R34") (pin "2") (pinfunction "2_2") (pintype "passive"))
      (node (ref "R35") (pin "2") (pinfunction "2_2") (pintype "passive"))
      (node (ref "R36") (pin "2") (pinfunction "2_2") (pintype "passive"))
      (node (ref "R37") (pin "2") (pinfunction "2_2") (pintype "passive"))
      (node (ref "R38") (pin "2") (pinfunction "2_2") (pintype "passive"))
      (node (ref "R39") (pin "2") (pinfunction "2_2") (pintype "passive"))
      (node (ref "RGB1") (pin "1") (pinfunction "VDD_1") (pintype "passive"))
      (node (ref "RGB2") (pin "1") (pinfunction "VDD_1") (pintype "passive"))
      (node (ref "RGB3") (pin "1") (pinfunction "VDD_1") (pintype "passive"))
      (node (ref "RGB4") (pin "1") (pinfunction "VDD_1") (pintype "passive"))
      (node (ref "RGB5") (pin "1") (pinfunction "VDD_1") (pintype "passive"))
      (node (ref "RGB6") (pin "1") (pinfunction "VDD_1") (pintype "passive"))
      (node (ref "U3") (pin "3") (pinfunction "OUT_3") (pintype "power_in"))
      (node (ref "U4") (pin "3") (pinfunction "IN_3") (pintype "passive"))
      (node (ref "U5") (pin "31") (pinfunction "~{BL}_31") (pintype "passive"))
      (node (ref "U5") (pin "32") (pinfunction "VDD_32") (pintype "passive"))
      (node (ref "U5") (pin "33") (pinfunction "DIR_33") (pintype "passive"))
    )
    (net (code "136") (name "VCC12") (class "Default")
      (node (ref "C22") (pin "1") (pinfunction "1_1") (pintype "passive"))
      (node (ref "C3") (pin "2") (pinfunction "2_2") (pintype "passive"))
      (node (ref "C5") (pin "2") (pinfunction "2_2") (pintype "passive"))
      (node (ref "D4") (pin "2") (pinfunction "K_2") (pintype "passive"))
      (node (ref "F1") (pin "2") (pinfunction "2_2") (pintype "passive"))
      (node (ref "R5") (pin "2") (pinfunction "2_2") (pintype "passive"))
      (node (ref "U1") (pin "6") (pinfunction "VCC_6") (pintype "passive"))
      (node (ref "U3") (pin "1") (pinfunction "IN_1") (pintype "power_in"))
    )
    (net (code "137") (name "VH") (class "Default")
      (node (ref "C4") (pin "1") (pinfunction "1_1") (pintype "passive"))
      (node (ref "D1") (pin "2") (pinfunction "K_2") (pintype "passive"))
      (node (ref "R10") (pin "2") (pinfunction "2_2") (pintype "passive"))
      (node (ref "R11") (pin "2") (pinfunction "2_2") (pintype "passive"))
      (node (ref "R12") (pin "1") (pinfunction "1_1") (pintype "passive"))
      (node (ref "R13") (pin "1") (pinfunction "1_1") (pintype "passive"))
      (node (ref "R14") (pin "2") (pinfunction "2_2") (pintype "passive"))
      (node (ref "R15") (pin "1") (pinfunction "1_1") (pintype "passive"))
      (node (ref "R2") (pin "1") (pinfunction "1_1") (pintype "passive"))
      (node (ref "R31") (pin "1") (pinfunction "1_1") (pintype "passive"))
      (node (ref "R6") (pin "2") (pinfunction "2_2") (pintype "passive"))
      (node (ref "R7") (pin "2") (pinfunction "2_2") (pintype "passive"))
      (node (ref "R8") (pin "2") (pinfunction "2_2") (pintype "passive"))
      (node (ref "R9") (pin "2") (pinfunction "2_2") (pintype "passive"))
    )
    (net (code "138") (name "unconnected-(J2-ID-Pad4)") (class "Default")
      (node (ref "J2") (pin "4") (pinfunction "ID_4") (pintype "passive"))
    )
    (net (code "139") (name "unconnected-(N1-LP-Pad2)") (class "Default")
      (node (ref "N1") (pin "2") (pinfunction "LP_2") (pintype "passive"))
    )
    (net (code "140") (name "unconnected-(N1-RP-Pad13)") (class "Default")
      (node (ref "N1") (pin "13") (pinfunction "RP_13") (pintype "passive"))
    )
    (net (code "141") (name "unconnected-(N2-LP-Pad2)") (class "Default")
      (node (ref "N2") (pin "2") (pinfunction "LP_2") (pintype "passive"))
    )
    (net (code "142") (name "unconnected-(N2-RP-Pad13)") (class "Default")
      (node (ref "N2") (pin "13") (pinfunction "RP_13") (pintype "passive"))
    )
    (net (code "143") (name "unconnected-(N3-LP-Pad2)") (class "Default")
      (node (ref "N3") (pin "2") (pinfunction "LP_2") (pintype "passive"))
    )
    (net (code "144") (name "unconnected-(N3-RP-Pad13)") (class "Default")
      (node (ref "N3") (pin "13") (pinfunction "RP_13") (pintype "passive"))
    )
    (net (code "145") (name "unconnected-(N4-LP-Pad2)") (class "Default")
      (node (ref "N4") (pin "2") (pinfunction "LP_2") (pintype "passive"))
    )
    (net (code "146") (name "unconnected-(N4-RP-Pad13)") (class "Default")
      (node (ref "N4") (pin "13") (pinfunction "RP_13") (pintype "passive"))
    )
    (net (code "147") (name "unconnected-(N5-LP-Pad2)") (class "Default")
      (node (ref "N5") (pin "2") (pinfunction "LP_2") (pintype "passive"))
    )
    (net (code "148") (name "unconnected-(N5-RP-Pad13)") (class "Default")
      (node (ref "N5") (pin "13") (pinfunction "RP_13") (pintype "passive"))
    )
    (net (code "149") (name "unconnected-(N6-LP-Pad2)") (class "Default")
      (node (ref "N6") (pin "2") (pinfunction "LP_2") (pintype "passive"))
    )
    (net (code "150") (name "unconnected-(N6-RP-Pad13)") (class "Default")
      (node (ref "N6") (pin "13") (pinfunction "RP_13") (pintype "passive"))
    )
    (net (code "151") (name "unconnected-(RGB6-DO-Pad2)") (class "Default")
      (node (ref "RGB6") (pin "2") (pinfunction "DO_2") (pintype "passive"))
    )
    (net (code "152") (name "unconnected-(U2-PA0-WKUP-Pad14)") (class "Default")
      (node (ref "U2") (pin "14") (pinfunction "PA0-WKUP_14") (pintype "bidirectional"))
    )
    (net (code "153") (name "unconnected-(U2-PA1-Pad15)") (class "Default")
      (node (ref "U2") (pin "15") (pinfunction "PA1_15") (pintype "bidirectional"))
    )
    (net (code "154") (name "unconnected-(U2-PA2-Pad16)") (class "Default")
      (node (ref "U2") (pin "16") (pinfunction "PA2_16") (pintype "bidirectional"))
    )
    (net (code "155") (name "unconnected-(U2-PA3-Pad17)") (class "Default")
      (node (ref "U2") (pin "17") (pinfunction "PA3_17") (pintype "bidirectional"))
    )
    (net (code "156") (name "unconnected-(U2-PA8-Pad41)") (class "Default")
      (node (ref "U2") (pin "41") (pinfunction "PA8_41") (pintype "bidirectional"))
    )
    (net (code "157") (name "unconnected-(U2-PB0-Pad26)") (class "Default")
      (node (ref "U2") (pin "26") (pinfunction "PB0_26") (pintype "bidirectional"))
    )
    (net (code "158") (name "unconnected-(U2-PB1-Pad27)") (class "Default")
      (node (ref "U2") (pin "27") (pinfunction "PB1_27") (pintype "bidirectional"))
    )
    (net (code "159") (name "unconnected-(U2-PB3{slash}JTDO-Pad55)") (class "Default")
      (node (ref "U2") (pin "55") (pinfunction "PB3/JTDO_55") (pintype "bidirectional"))
    )
    (net (code "160") (name "unconnected-(U2-PB6-Pad58)") (class "Default")
      (node (ref "U2") (pin "58") (pinfunction "PB6_58") (pintype "bidirectional"))
    )
    (net (code "161") (name "unconnected-(U2-PB7-Pad59)") (class "Default")
      (node (ref "U2") (pin "59") (pinfunction "PB7_59") (pintype "bidirectional"))
    )
    (net (code "162") (name "unconnected-(U2-PB8-Pad61)") (class "Default")
      (node (ref "U2") (pin "61") (pinfunction "PB8_61") (pintype "bidirectional"))
    )
    (net (code "163") (name "unconnected-(U2-PB9-Pad62)") (class "Default")
      (node (ref "U2") (pin "62") (pinfunction "PB9_62") (pintype "bidirectional"))
    )
    (net (code "164") (name "unconnected-(U2-PC4-Pad24)") (class "Default")
      (node (ref "U2") (pin "24") (pinfunction "PC4_24") (pintype "bidirectional"))
    )
    (net (code "165") (name "unconnected-(U2-PC5-Pad25)") (class "Default")
      (node (ref "U2") (pin "25") (pinfunction "PC5_25") (pintype "bidirectional"))
    )
    (net (code "166") (name "unconnected-(U2-PC7-Pad38)") (class "Default")
      (node (ref "U2") (pin "38") (pinfunction "PC7_38") (pintype "bidirectional"))
    )
    (net (code "167") (name "unconnected-(U2-PC8-Pad39)") (class "Default")
      (node (ref "U2") (pin "39") (pinfunction "PC8_39") (pintype "bidirectional"))
    )
    (net (code "168") (name "unconnected-(U2-PC14-OSC32_IN-Pad3)") (class "Default")
      (node (ref "U2") (pin "3") (pinfunction "PC14-OSC32_IN_3") (pintype "bidirectional"))
    )
    (net (code "169") (name "unconnected-(U2-PC15-OSC32_OUT-Pad4)") (class "Default")
      (node (ref "U2") (pin "4") (pinfunction "PC15-OSC32_OUT_4") (pintype "bidirectional"))
    )
    (net (code "170") (name "unconnected-(U2-PD2-Pad54)") (class "Default")
      (node (ref "U2") (pin "54") (pinfunction "PD2_54") (pintype "bidirectional"))
    )
    (net (code "171") (name "unconnected-(U5-DOUT1{slash}DIN4(B)-Pad39)") (class "Default")
      (node (ref "U5") (pin "39") (pinfunction "DOUT1/DIN4(B)_39") (pintype "passive"))
    )
    (net (code "172") (name "unconnected-(U5-DOUT2{slash}DIN3(B)-Pad38)") (class "Default")
      (node (ref "U5") (pin "38") (pinfunction "DOUT2/DIN3(B)_38") (pintype "passive"))
    )
    (net (code "173") (name "unconnected-(U5-DOUT3{slash}DIN2(B)-Pad37)") (class "Default")
      (node (ref "U5") (pin "37") (pinfunction "DOUT3/DIN2(B)_37") (pintype "passive"))
    )
    (net (code "174") (name "unconnected-(U5-DOUT4{slash}DIN1(B)-Pad36)") (class "Default")
      (node (ref "U5") (pin "36") (pinfunction "DOUT4/DIN1(B)_36") (pintype "passive"))
    )
    (net (code "175") (name "unconnected-(U5-HVOUT61{slash}4-Pad44)") (class "Default")
      (node (ref "U5") (pin "44") (pinfunction "HVOUT61/4_44") (pintype "passive"))
    )
    (net (code "176") (name "unconnected-(U5-HVOUT62{slash}3-Pad43)") (class "Default")
      (node (ref "U5") (pin "43") (pinfunction "HVOUT62/3_43") (pintype "passive"))
    )
    (net (code "177") (name "unconnected-(U5-HVOUT63{slash}2-Pad42)") (class "Default")
      (node (ref "U5") (pin "42") (pinfunction "HVOUT63/2_42") (pintype "passive"))
    )
    (net (code "178") (name "unconnected-(U5-HVOUT64{slash}1-Pad41)") (class "Default")
      (node (ref "U5") (pin "41") (pinfunction "HVOUT64/1_41") (pintype "passive"))
    )
    (net (code "179") (name "unconnected-(U6-32kHz-Pad1)") (class "Default")
      (node (ref "U6") (pin "1") (pinfunction "32kHz_1") (pintype "passive"))
    )
    (net (code "180") (name "unconnected-(U6-~{RST}-Pad4)") (class "Default")
      (node (ref "U6") (pin "4") (pinfunction "~{RST}_4") (pintype "passive"))
    )
    (net (code "181") (name "unconnected-(U8-KEY--Pad15)") (class "Default")
      (node (ref "U8") (pin "15") (pinfunction "KEY-_15") (pintype "passive"))
    )
    (net (code "182") (name "unconnected-(U8-LED-Pad16)") (class "Default")
      (node (ref "U8") (pin "16") (pinfunction "LED_16") (pintype "passive"))
    )
    (net (code "183") (name "unconnected-(U8-LEDCON-Pad14)") (class "Default")
      (node (ref "U8") (pin "14") (pinfunction "LEDCON_14") (pintype "passive"))
    )
    (net (code "184") (name "unconnected-(U8-NC-Pad3)") (class "Default")
      (node (ref "U8") (pin "3") (pinfunction "NC_3") (pintype "passive"))
    )
    (net (code "185") (name "unconnected-(U8-NC-Pad4)") (class "Default")
      (node (ref "U8") (pin "4") (pinfunction "NC_4") (pintype "passive"))
    )
    (net (code "186") (name "unconnected-(U8-NC-Pad5)") (class "Default")
      (node (ref "U8") (pin "5") (pinfunction "NC_5") (pintype "passive"))
    )
    (net (code "187") (name "unconnected-(U8-NC-Pad6)") (class "Default")
      (node (ref "U8") (pin "6") (pinfunction "NC_6") (pintype "passive"))
    )
    (net (code "188") (name "unconnected-(U8-NC-Pad7)") (class "Default")
      (node (ref "U8") (pin "7") (pinfunction "NC_7") (pintype "passive"))
    )
    (net (code "189") (name "unconnected-(U8-NC-Pad8)") (class "Default")
      (node (ref "U8") (pin "8") (pinfunction "NC_8") (pintype "passive"))
    )
    (net (code "190") (name "unconnected-(U8-NC-Pad9)") (class "Default")
      (node (ref "U8") (pin "9") (pinfunction "NC_9") (pintype "passive"))
    )
    (net (code "191") (name "unconnected-(U8-NC-Pad10)") (class "Default")
      (node (ref "U8") (pin "10") (pinfunction "NC_10") (pintype "passive"))
    )
    (net (code "192") (name "unconnected-(U8-NC-Pad19)") (class "Default")
      (node (ref "U8") (pin "19") (pinfunction "NC_19") (pintype "passive"))
    )
    (net (code "193") (name "unconnected-(U8-NC-Pad20)") (class "Default")
      (node (ref "U8") (pin "20") (pinfunction "NC_20") (pintype "passive"))
    )
    (net (code "194") (name "unconnected-(U8-NC-Pad21)") (class "Default")
      (node (ref "U8") (pin "21") (pinfunction "NC_21") (pintype "passive"))
    )
    (net (code "195") (name "unconnected-(U8-NC-Pad22)") (class "Default")
      (node (ref "U8") (pin "22") (pinfunction "NC_22") (pintype "passive"))
    )
    (net (code "196") (name "unconnected-(U8-NC-Pad23)") (class "Default")
      (node (ref "U8") (pin "23") (pinfunction "NC_23") (pintype "passive"))
    )
    (net (code "197") (name "unconnected-(U8-NC-Pad24)") (class "Default")
      (node (ref "U8") (pin "24") (pinfunction "NC_24") (pintype "passive"))
    )
    (net (code "198") (name "unconnected-(U8-NC-Pad25)") (class "Default")
      (node (ref "U8") (pin "25") (pinfunction "NC_25") (pintype "passive"))
    )
    (net (code "199") (name "unconnected-(U8-NC-Pad26)") (class "Default")
      (node (ref "U8") (pin "26") (pinfunction "NC_26") (pintype "passive"))
    )
    (net (code "200") (name "unconnected-(U8-~{RST}-Pad11)") (class "Default")
      (node (ref "U8") (pin "11") (pinfunction "~{RST}_11") (pintype "passive"))
    )
  )
)
